# ZYNQ_Power.net
KiCad netlist of a schematic drawn in Altium Designer
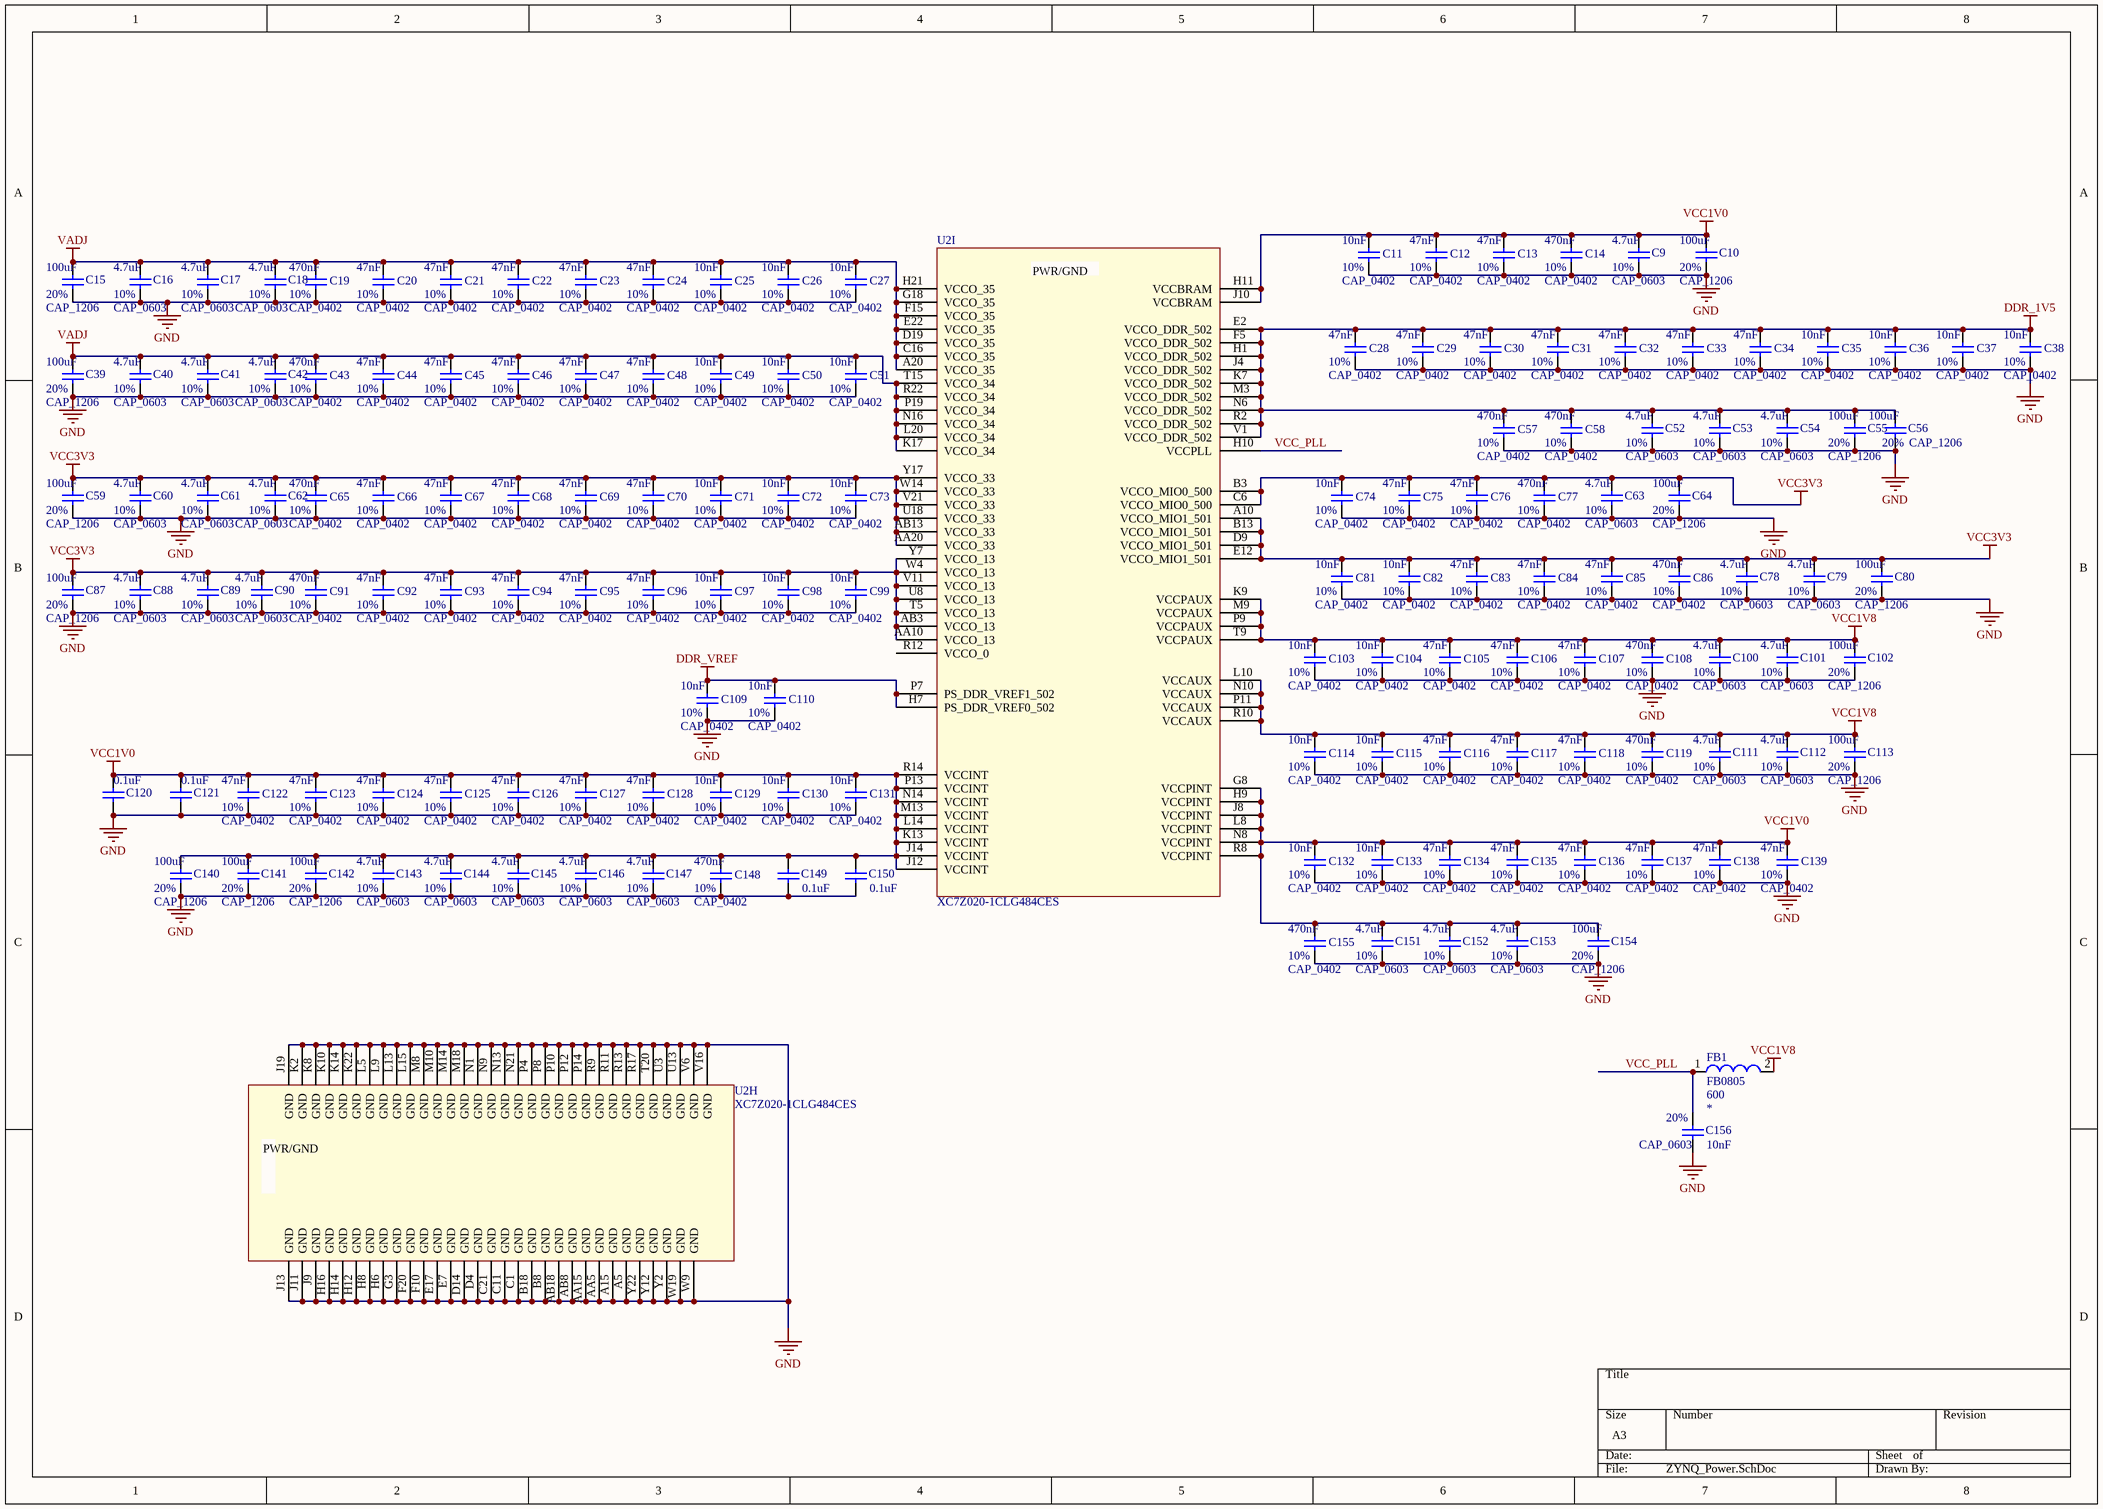
[diagram p0: ZYNQ_Power.SchDoc]

(export (version "E")
  (design (tool "Eeschema 10.0.6"))
  (components
    (comp (ref "C9")
      (value "CAP_0603")
      (footprint "CAPC0603(1608)100_N:CAPC0603(1608)100_N")
      (description "4.7uF, ceramic, 10% 6.3V X5R Low ESR, 0603")
      (fields
        (field (name "ALTIUM_VALUE") "4.7uF")
        (field (name "TOLERANCE") "10%")
        (field (name "PART NUMBER") "GRM188R60J475KE19D")
        (field (name "MANUFACTURER") "Murata Electronics North America")
      )
      (libsource (lib "COMRAD_Database") (part "CAP_0603"))
    )
    (comp (ref "C10")
      (value "CAP_1206")
      (footprint "CAPC1206(3216)100_N:CAPC1206(3216)100_N")
      (description "CAP CER 100UF 6.3V 20% X5R 1206")
      (fields
        (field (name "ALTIUM_VALUE") "100uF")
        (field (name "TOLERANCE") "20%")
        (field (name "PART NUMBER") "JMK316BJ107ML-T")
        (field (name "MANUFACTURER") "Taiyo Yuden")
      )
      (libsource (lib "COMRAD_Database") (part "CAP_1206"))
    )
    (comp (ref "C11")
      (value "CAP_0402")
      (footprint "CAPC0402(1005)60_N:CAPC0402(1005)60_N")
      (description "10000pF, ceramic, 10% 6.3V X5R, 0402")
      (fields
        (field (name "ALTIUM_VALUE") "10nF")
        (field (name "TOLERANCE") "10%")
        (field (name "PART NUMBER") "GRM155R60J103KA01D")
        (field (name "MANUFACTURER") "Murata Electronics North America")
      )
      (libsource (lib "COMRAD_Database") (part "CAP_0402"))
    )
    (comp (ref "C12")
      (value "CAP_0402")
      (footprint "CAPC0402(1005)60_N:CAPC0402(1005)60_N")
      (description "0.047uF, ceramic, 10% 6.3V X5R, 0402")
      (fields
        (field (name "ALTIUM_VALUE") "47nF")
        (field (name "TOLERANCE") "10%")
        (field (name "PART NUMBER") "GRM155R60J473KA01D")
        (field (name "MANUFACTURER") "Murata Electronics North America")
      )
      (libsource (lib "COMRAD_Database") (part "CAP_0402"))
    )
    (comp (ref "C13")
      (value "CAP_0402")
      (footprint "CAPC0402(1005)60_N:CAPC0402(1005)60_N")
      (description "0.047uF, ceramic, 10% 6.3V X5R, 0402")
      (fields
        (field (name "ALTIUM_VALUE") "47nF")
        (field (name "TOLERANCE") "10%")
        (field (name "PART NUMBER") "GRM155R60J473KA01D")
        (field (name "MANUFACTURER") "Murata Electronics North America")
      )
      (libsource (lib "COMRAD_Database") (part "CAP_0402"))
    )
    (comp (ref "C14")
      (value "CAP_0402")
      (footprint "CAPC0402(1005)60_N:CAPC0402(1005)60_N")
      (description "0.47uF, ceramic, 10% 6.3V X5R, 0402")
      (fields
        (field (name "ALTIUM_VALUE") "470nF")
        (field (name "TOLERANCE") "10%")
        (field (name "PART NUMBER") "GRM155R60J474KE19D")
        (field (name "MANUFACTURER") "Murata Electronics North America")
      )
      (libsource (lib "COMRAD_Database") (part "CAP_0402"))
    )
    (comp (ref "C15")
      (value "CAP_1206")
      (footprint "CAPC1206(3216)100_N:CAPC1206(3216)100_N")
      (description "CAP CER 100UF 6.3V 20% X5R 1206")
      (fields
        (field (name "ALTIUM_VALUE") "100uF")
        (field (name "TOLERANCE") "20%")
        (field (name "PART NUMBER") "JMK316BJ107ML-T")
        (field (name "MANUFACTURER") "Taiyo Yuden")
      )
      (libsource (lib "COMRAD_Database") (part "CAP_1206"))
    )
    (comp (ref "C16")
      (value "CAP_0603")
      (footprint "CAPC0603(1608)100_N:CAPC0603(1608)100_N")
      (description "4.7uF, ceramic, 10% 6.3V X5R Low ESR, 0603")
      (fields
        (field (name "ALTIUM_VALUE") "4.7uF")
        (field (name "TOLERANCE") "10%")
        (field (name "PART NUMBER") "GRM188R60J475KE19D")
        (field (name "MANUFACTURER") "Murata Electronics North America")
      )
      (libsource (lib "COMRAD_Database") (part "CAP_0603"))
    )
    (comp (ref "C17")
      (value "CAP_0603")
      (footprint "CAPC0603(1608)100_N:CAPC0603(1608)100_N")
      (description "4.7uF, ceramic, 10% 6.3V X5R Low ESR, 0603")
      (fields
        (field (name "ALTIUM_VALUE") "4.7uF")
        (field (name "TOLERANCE") "10%")
        (field (name "PART NUMBER") "GRM188R60J475KE19D")
        (field (name "MANUFACTURER") "Murata Electronics North America")
      )
      (libsource (lib "COMRAD_Database") (part "CAP_0603"))
    )
    (comp (ref "C18")
      (value "CAP_0603")
      (footprint "CAPC0603(1608)100_N:CAPC0603(1608)100_N")
      (description "4.7uF, ceramic, 10% 6.3V X5R Low ESR, 0603")
      (fields
        (field (name "ALTIUM_VALUE") "4.7uF")
        (field (name "TOLERANCE") "10%")
        (field (name "PART NUMBER") "GRM188R60J475KE19D")
        (field (name "MANUFACTURER") "Murata Electronics North America")
      )
      (libsource (lib "COMRAD_Database") (part "CAP_0603"))
    )
    (comp (ref "C19")
      (value "CAP_0402")
      (footprint "CAPC0402(1005)60_N:CAPC0402(1005)60_N")
      (description "0.47uF, ceramic, 10% 6.3V X5R, 0402")
      (fields
        (field (name "ALTIUM_VALUE") "470nF")
        (field (name "TOLERANCE") "10%")
        (field (name "PART NUMBER") "GRM155R60J474KE19D")
        (field (name "MANUFACTURER") "Murata Electronics North America")
      )
      (libsource (lib "COMRAD_Database") (part "CAP_0402"))
    )
    (comp (ref "C20")
      (value "CAP_0402")
      (footprint "CAPC0402(1005)60_N:CAPC0402(1005)60_N")
      (description "0.047uF, ceramic, 10% 6.3V X5R, 0402")
      (fields
        (field (name "ALTIUM_VALUE") "47nF")
        (field (name "TOLERANCE") "10%")
        (field (name "PART NUMBER") "GRM155R60J473KA01D")
        (field (name "MANUFACTURER") "Murata Electronics North America")
      )
      (libsource (lib "COMRAD_Database") (part "CAP_0402"))
    )
    (comp (ref "C21")
      (value "CAP_0402")
      (footprint "CAPC0402(1005)60_N:CAPC0402(1005)60_N")
      (description "0.047uF, ceramic, 10% 6.3V X5R, 0402")
      (fields
        (field (name "ALTIUM_VALUE") "47nF")
        (field (name "TOLERANCE") "10%")
        (field (name "PART NUMBER") "GRM155R60J473KA01D")
        (field (name "MANUFACTURER") "Murata Electronics North America")
      )
      (libsource (lib "COMRAD_Database") (part "CAP_0402"))
    )
    (comp (ref "C22")
      (value "CAP_0402")
      (footprint "CAPC0402(1005)60_N:CAPC0402(1005)60_N")
      (description "0.047uF, ceramic, 10% 6.3V X5R, 0402")
      (fields
        (field (name "ALTIUM_VALUE") "47nF")
        (field (name "TOLERANCE") "10%")
        (field (name "PART NUMBER") "GRM155R60J473KA01D")
        (field (name "MANUFACTURER") "Murata Electronics North America")
      )
      (libsource (lib "COMRAD_Database") (part "CAP_0402"))
    )
    (comp (ref "C23")
      (value "CAP_0402")
      (footprint "CAPC0402(1005)60_N:CAPC0402(1005)60_N")
      (description "0.047uF, ceramic, 10% 6.3V X5R, 0402")
      (fields
        (field (name "ALTIUM_VALUE") "47nF")
        (field (name "TOLERANCE") "10%")
        (field (name "PART NUMBER") "GRM155R60J473KA01D")
        (field (name "MANUFACTURER") "Murata Electronics North America")
      )
      (libsource (lib "COMRAD_Database") (part "CAP_0402"))
    )
    (comp (ref "C24")
      (value "CAP_0402")
      (footprint "CAPC0402(1005)60_N:CAPC0402(1005)60_N")
      (description "0.047uF, ceramic, 10% 6.3V X5R, 0402")
      (fields
        (field (name "ALTIUM_VALUE") "47nF")
        (field (name "TOLERANCE") "10%")
        (field (name "PART NUMBER") "GRM155R60J473KA01D")
        (field (name "MANUFACTURER") "Murata Electronics North America")
      )
      (libsource (lib "COMRAD_Database") (part "CAP_0402"))
    )
    (comp (ref "C25")
      (value "CAP_0402")
      (footprint "CAPC0402(1005)60_N:CAPC0402(1005)60_N")
      (description "10000pF, ceramic, 10% 6.3V X5R, 0402")
      (fields
        (field (name "ALTIUM_VALUE") "10nF")
        (field (name "TOLERANCE") "10%")
        (field (name "PART NUMBER") "GRM155R60J103KA01D")
        (field (name "MANUFACTURER") "Murata Electronics North America")
      )
      (libsource (lib "COMRAD_Database") (part "CAP_0402"))
    )
    (comp (ref "C26")
      (value "CAP_0402")
      (footprint "CAPC0402(1005)60_N:CAPC0402(1005)60_N")
      (description "10000pF, ceramic, 10% 6.3V X5R, 0402")
      (fields
        (field (name "ALTIUM_VALUE") "10nF")
        (field (name "TOLERANCE") "10%")
        (field (name "PART NUMBER") "GRM155R60J103KA01D")
        (field (name "MANUFACTURER") "Murata Electronics North America")
      )
      (libsource (lib "COMRAD_Database") (part "CAP_0402"))
    )
    (comp (ref "C27")
      (value "CAP_0402")
      (footprint "CAPC0402(1005)60_N:CAPC0402(1005)60_N")
      (description "10000pF, ceramic, 10% 6.3V X5R, 0402")
      (fields
        (field (name "ALTIUM_VALUE") "10nF")
        (field (name "TOLERANCE") "10%")
        (field (name "PART NUMBER") "GRM155R60J103KA01D")
        (field (name "MANUFACTURER") "Murata Electronics North America")
      )
      (libsource (lib "COMRAD_Database") (part "CAP_0402"))
    )
    (comp (ref "C28")
      (value "CAP_0402")
      (footprint "CAPC0402(1005)60_N:CAPC0402(1005)60_N")
      (description "0.047uF, ceramic, 10% 6.3V X5R, 0402")
      (fields
        (field (name "ALTIUM_VALUE") "47nF")
        (field (name "TOLERANCE") "10%")
        (field (name "PART NUMBER") "GRM155R60J473KA01D")
        (field (name "MANUFACTURER") "Murata Electronics North America")
      )
      (libsource (lib "COMRAD_Database") (part "CAP_0402"))
    )
    (comp (ref "C29")
      (value "CAP_0402")
      (footprint "CAPC0402(1005)60_N:CAPC0402(1005)60_N")
      (description "0.047uF, ceramic, 10% 6.3V X5R, 0402")
      (fields
        (field (name "ALTIUM_VALUE") "47nF")
        (field (name "TOLERANCE") "10%")
        (field (name "PART NUMBER") "GRM155R60J473KA01D")
        (field (name "MANUFACTURER") "Murata Electronics North America")
      )
      (libsource (lib "COMRAD_Database") (part "CAP_0402"))
    )
    (comp (ref "C30")
      (value "CAP_0402")
      (footprint "CAPC0402(1005)60_N:CAPC0402(1005)60_N")
      (description "0.047uF, ceramic, 10% 6.3V X5R, 0402")
      (fields
        (field (name "ALTIUM_VALUE") "47nF")
        (field (name "TOLERANCE") "10%")
        (field (name "PART NUMBER") "GRM155R60J473KA01D")
        (field (name "MANUFACTURER") "Murata Electronics North America")
      )
      (libsource (lib "COMRAD_Database") (part "CAP_0402"))
    )
    (comp (ref "C31")
      (value "CAP_0402")
      (footprint "CAPC0402(1005)60_N:CAPC0402(1005)60_N")
      (description "0.047uF, ceramic, 10% 6.3V X5R, 0402")
      (fields
        (field (name "ALTIUM_VALUE") "47nF")
        (field (name "TOLERANCE") "10%")
        (field (name "PART NUMBER") "GRM155R60J473KA01D")
        (field (name "MANUFACTURER") "Murata Electronics North America")
      )
      (libsource (lib "COMRAD_Database") (part "CAP_0402"))
    )
    (comp (ref "C32")
      (value "CAP_0402")
      (footprint "CAPC0402(1005)60_N:CAPC0402(1005)60_N")
      (description "0.047uF, ceramic, 10% 6.3V X5R, 0402")
      (fields
        (field (name "ALTIUM_VALUE") "47nF")
        (field (name "TOLERANCE") "10%")
        (field (name "PART NUMBER") "GRM155R60J473KA01D")
        (field (name "MANUFACTURER") "Murata Electronics North America")
      )
      (libsource (lib "COMRAD_Database") (part "CAP_0402"))
    )
    (comp (ref "C33")
      (value "CAP_0402")
      (footprint "CAPC0402(1005)60_N:CAPC0402(1005)60_N")
      (description "0.047uF, ceramic, 10% 6.3V X5R, 0402")
      (fields
        (field (name "ALTIUM_VALUE") "47nF")
        (field (name "TOLERANCE") "10%")
        (field (name "PART NUMBER") "GRM155R60J473KA01D")
        (field (name "MANUFACTURER") "Murata Electronics North America")
      )
      (libsource (lib "COMRAD_Database") (part "CAP_0402"))
    )
    (comp (ref "C34")
      (value "CAP_0402")
      (footprint "CAPC0402(1005)60_N:CAPC0402(1005)60_N")
      (description "0.047uF, ceramic, 10% 6.3V X5R, 0402")
      (fields
        (field (name "ALTIUM_VALUE") "47nF")
        (field (name "TOLERANCE") "10%")
        (field (name "PART NUMBER") "GRM155R60J473KA01D")
        (field (name "MANUFACTURER") "Murata Electronics North America")
      )
      (libsource (lib "COMRAD_Database") (part "CAP_0402"))
    )
    (comp (ref "C35")
      (value "CAP_0402")
      (footprint "CAPC0402(1005)60_N:CAPC0402(1005)60_N")
      (description "10000pF, ceramic, 10% 6.3V X5R, 0402")
      (fields
        (field (name "ALTIUM_VALUE") "10nF")
        (field (name "TOLERANCE") "10%")
        (field (name "PART NUMBER") "GRM155R60J103KA01D")
        (field (name "MANUFACTURER") "Murata Electronics North America")
      )
      (libsource (lib "COMRAD_Database") (part "CAP_0402"))
    )
    (comp (ref "C36")
      (value "CAP_0402")
      (footprint "CAPC0402(1005)60_N:CAPC0402(1005)60_N")
      (description "10000pF, ceramic, 10% 6.3V X5R, 0402")
      (fields
        (field (name "ALTIUM_VALUE") "10nF")
        (field (name "TOLERANCE") "10%")
        (field (name "PART NUMBER") "GRM155R60J103KA01D")
        (field (name "MANUFACTURER") "Murata Electronics North America")
      )
      (libsource (lib "COMRAD_Database") (part "CAP_0402"))
    )
    (comp (ref "C37")
      (value "CAP_0402")
      (footprint "CAPC0402(1005)60_N:CAPC0402(1005)60_N")
      (description "10000pF, ceramic, 10% 6.3V X5R, 0402")
      (fields
        (field (name "ALTIUM_VALUE") "10nF")
        (field (name "TOLERANCE") "10%")
        (field (name "PART NUMBER") "GRM155R60J103KA01D")
        (field (name "MANUFACTURER") "Murata Electronics North America")
      )
      (libsource (lib "COMRAD_Database") (part "CAP_0402"))
    )
    (comp (ref "C38")
      (value "CAP_0402")
      (footprint "CAPC0402(1005)60_N:CAPC0402(1005)60_N")
      (description "10000pF, ceramic, 10% 6.3V X5R, 0402")
      (fields
        (field (name "ALTIUM_VALUE") "10nF")
        (field (name "TOLERANCE") "10%")
        (field (name "PART NUMBER") "GRM155R60J103KA01D")
        (field (name "MANUFACTURER") "Murata Electronics North America")
      )
      (libsource (lib "COMRAD_Database") (part "CAP_0402"))
    )
    (comp (ref "C39")
      (value "CAP_1206")
      (footprint "CAPC1206(3216)100_N:CAPC1206(3216)100_N")
      (description "CAP CER 100UF 6.3V 20% X5R 1206")
      (fields
        (field (name "ALTIUM_VALUE") "100uF")
        (field (name "TOLERANCE") "20%")
        (field (name "PART NUMBER") "JMK316BJ107ML-T")
        (field (name "MANUFACTURER") "Taiyo Yuden")
      )
      (libsource (lib "COMRAD_Database") (part "CAP_1206"))
    )
    (comp (ref "C40")
      (value "CAP_0603")
      (footprint "CAPC0603(1608)100_N:CAPC0603(1608)100_N")
      (description "4.7uF, ceramic, 10% 6.3V X5R Low ESR, 0603")
      (fields
        (field (name "ALTIUM_VALUE") "4.7uF")
        (field (name "TOLERANCE") "10%")
        (field (name "PART NUMBER") "GRM188R60J475KE19D")
        (field (name "MANUFACTURER") "Murata Electronics North America")
      )
      (libsource (lib "COMRAD_Database") (part "CAP_0603"))
    )
    (comp (ref "C41")
      (value "CAP_0603")
      (footprint "CAPC0603(1608)100_N:CAPC0603(1608)100_N")
      (description "4.7uF, ceramic, 10% 6.3V X5R Low ESR, 0603")
      (fields
        (field (name "ALTIUM_VALUE") "4.7uF")
        (field (name "TOLERANCE") "10%")
        (field (name "PART NUMBER") "GRM188R60J475KE19D")
        (field (name "MANUFACTURER") "Murata Electronics North America")
      )
      (libsource (lib "COMRAD_Database") (part "CAP_0603"))
    )
    (comp (ref "C42")
      (value "CAP_0603")
      (footprint "CAPC0603(1608)100_N:CAPC0603(1608)100_N")
      (description "4.7uF, ceramic, 10% 6.3V X5R Low ESR, 0603")
      (fields
        (field (name "ALTIUM_VALUE") "4.7uF")
        (field (name "TOLERANCE") "10%")
        (field (name "PART NUMBER") "GRM188R60J475KE19D")
        (field (name "MANUFACTURER") "Murata Electronics North America")
      )
      (libsource (lib "COMRAD_Database") (part "CAP_0603"))
    )
    (comp (ref "C43")
      (value "CAP_0402")
      (footprint "CAPC0402(1005)60_N:CAPC0402(1005)60_N")
      (description "0.47uF, ceramic, 10% 6.3V X5R, 0402")
      (fields
        (field (name "ALTIUM_VALUE") "470nF")
        (field (name "TOLERANCE") "10%")
        (field (name "PART NUMBER") "GRM155R60J474KE19D")
        (field (name "MANUFACTURER") "Murata Electronics North America")
      )
      (libsource (lib "COMRAD_Database") (part "CAP_0402"))
    )
    (comp (ref "C44")
      (value "CAP_0402")
      (footprint "CAPC0402(1005)60_N:CAPC0402(1005)60_N")
      (description "0.047uF, ceramic, 10% 6.3V X5R, 0402")
      (fields
        (field (name "ALTIUM_VALUE") "47nF")
        (field (name "TOLERANCE") "10%")
        (field (name "PART NUMBER") "GRM155R60J473KA01D")
        (field (name "MANUFACTURER") "Murata Electronics North America")
      )
      (libsource (lib "COMRAD_Database") (part "CAP_0402"))
    )
    (comp (ref "C45")
      (value "CAP_0402")
      (footprint "CAPC0402(1005)60_N:CAPC0402(1005)60_N")
      (description "0.047uF, ceramic, 10% 6.3V X5R, 0402")
      (fields
        (field (name "ALTIUM_VALUE") "47nF")
        (field (name "TOLERANCE") "10%")
        (field (name "PART NUMBER") "GRM155R60J473KA01D")
        (field (name "MANUFACTURER") "Murata Electronics North America")
      )
      (libsource (lib "COMRAD_Database") (part "CAP_0402"))
    )
    (comp (ref "C46")
      (value "CAP_0402")
      (footprint "CAPC0402(1005)60_N:CAPC0402(1005)60_N")
      (description "0.047uF, ceramic, 10% 6.3V X5R, 0402")
      (fields
        (field (name "ALTIUM_VALUE") "47nF")
        (field (name "TOLERANCE") "10%")
        (field (name "PART NUMBER") "GRM155R60J473KA01D")
        (field (name "MANUFACTURER") "Murata Electronics North America")
      )
      (libsource (lib "COMRAD_Database") (part "CAP_0402"))
    )
    (comp (ref "C47")
      (value "CAP_0402")
      (footprint "CAPC0402(1005)60_N:CAPC0402(1005)60_N")
      (description "0.047uF, ceramic, 10% 6.3V X5R, 0402")
      (fields
        (field (name "ALTIUM_VALUE") "47nF")
        (field (name "TOLERANCE") "10%")
        (field (name "PART NUMBER") "GRM155R60J473KA01D")
        (field (name "MANUFACTURER") "Murata Electronics North America")
      )
      (libsource (lib "COMRAD_Database") (part "CAP_0402"))
    )
    (comp (ref "C48")
      (value "CAP_0402")
      (footprint "CAPC0402(1005)60_N:CAPC0402(1005)60_N")
      (description "0.047uF, ceramic, 10% 6.3V X5R, 0402")
      (fields
        (field (name "ALTIUM_VALUE") "47nF")
        (field (name "TOLERANCE") "10%")
        (field (name "PART NUMBER") "GRM155R60J473KA01D")
        (field (name "MANUFACTURER") "Murata Electronics North America")
      )
      (libsource (lib "COMRAD_Database") (part "CAP_0402"))
    )
    (comp (ref "C49")
      (value "CAP_0402")
      (footprint "CAPC0402(1005)60_N:CAPC0402(1005)60_N")
      (description "10000pF, ceramic, 10% 6.3V X5R, 0402")
      (fields
        (field (name "ALTIUM_VALUE") "10nF")
        (field (name "TOLERANCE") "10%")
        (field (name "PART NUMBER") "GRM155R60J103KA01D")
        (field (name "MANUFACTURER") "Murata Electronics North America")
      )
      (libsource (lib "COMRAD_Database") (part "CAP_0402"))
    )
    (comp (ref "C50")
      (value "CAP_0402")
      (footprint "CAPC0402(1005)60_N:CAPC0402(1005)60_N")
      (description "10000pF, ceramic, 10% 6.3V X5R, 0402")
      (fields
        (field (name "ALTIUM_VALUE") "10nF")
        (field (name "TOLERANCE") "10%")
        (field (name "PART NUMBER") "GRM155R60J103KA01D")
        (field (name "MANUFACTURER") "Murata Electronics North America")
      )
      (libsource (lib "COMRAD_Database") (part "CAP_0402"))
    )
    (comp (ref "C51")
      (value "CAP_0402")
      (footprint "CAPC0402(1005)60_N:CAPC0402(1005)60_N")
      (description "10000pF, ceramic, 10% 6.3V X5R, 0402")
      (fields
        (field (name "ALTIUM_VALUE") "10nF")
        (field (name "TOLERANCE") "10%")
        (field (name "PART NUMBER") "GRM155R60J103KA01D")
        (field (name "MANUFACTURER") "Murata Electronics North America")
      )
      (libsource (lib "COMRAD_Database") (part "CAP_0402"))
    )
    (comp (ref "C52")
      (value "CAP_0603")
      (footprint "CAPC0603(1608)100_N:CAPC0603(1608)100_N")
      (description "4.7uF, ceramic, 10% 6.3V X5R Low ESR, 0603")
      (fields
        (field (name "ALTIUM_VALUE") "4.7uF")
        (field (name "TOLERANCE") "10%")
        (field (name "PART NUMBER") "GRM188R60J475KE19D")
        (field (name "MANUFACTURER") "Murata Electronics North America")
      )
      (libsource (lib "COMRAD_Database") (part "CAP_0603"))
    )
    (comp (ref "C53")
      (value "CAP_0603")
      (footprint "CAPC0603(1608)100_N:CAPC0603(1608)100_N")
      (description "4.7uF, ceramic, 10% 6.3V X5R Low ESR, 0603")
      (fields
        (field (name "ALTIUM_VALUE") "4.7uF")
        (field (name "TOLERANCE") "10%")
        (field (name "PART NUMBER") "GRM188R60J475KE19D")
        (field (name "MANUFACTURER") "Murata Electronics North America")
      )
      (libsource (lib "COMRAD_Database") (part "CAP_0603"))
    )
    (comp (ref "C54")
      (value "CAP_0603")
      (footprint "CAPC0603(1608)100_N:CAPC0603(1608)100_N")
      (description "4.7uF, ceramic, 10% 6.3V X5R Low ESR, 0603")
      (fields
        (field (name "ALTIUM_VALUE") "4.7uF")
        (field (name "TOLERANCE") "10%")
        (field (name "PART NUMBER") "GRM188R60J475KE19D")
        (field (name "MANUFACTURER") "Murata Electronics North America")
      )
      (libsource (lib "COMRAD_Database") (part "CAP_0603"))
    )
    (comp (ref "C55")
      (value "CAP_1206")
      (footprint "CAPC1206(3216)100_N:CAPC1206(3216)100_N")
      (description "CAP CER 100UF 6.3V 20% X5R 1206")
      (fields
        (field (name "ALTIUM_VALUE") "100uF")
        (field (name "TOLERANCE") "20%")
        (field (name "PART NUMBER") "JMK316BJ107ML-T")
        (field (name "MANUFACTURER") "Taiyo Yuden")
      )
      (libsource (lib "COMRAD_Database") (part "CAP_1206"))
    )
    (comp (ref "C56")
      (value "CAP_1206")
      (footprint "CAPC1206(3216)100_N:CAPC1206(3216)100_N")
      (description "CAP CER 100UF 6.3V 20% X5R 1206")
      (fields
        (field (name "ALTIUM_VALUE") "100uF")
        (field (name "TOLERANCE") "20%")
        (field (name "PART NUMBER") "JMK316BJ107ML-T")
        (field (name "MANUFACTURER") "Taiyo Yuden")
      )
      (libsource (lib "COMRAD_Database") (part "CAP_1206"))
    )
    (comp (ref "C57")
      (value "CAP_0402")
      (footprint "CAPC0402(1005)60_N:CAPC0402(1005)60_N")
      (description "0.47uF, ceramic, 10% 6.3V X5R, 0402")
      (fields
        (field (name "ALTIUM_VALUE") "470nF")
        (field (name "TOLERANCE") "10%")
        (field (name "PART NUMBER") "GRM155R60J474KE19D")
        (field (name "MANUFACTURER") "Murata Electronics North America")
      )
      (libsource (lib "COMRAD_Database") (part "CAP_0402"))
    )
    (comp (ref "C58")
      (value "CAP_0402")
      (footprint "CAPC0402(1005)60_N:CAPC0402(1005)60_N")
      (description "0.47uF, ceramic, 10% 6.3V X5R, 0402")
      (fields
        (field (name "ALTIUM_VALUE") "470nF")
        (field (name "TOLERANCE") "10%")
        (field (name "PART NUMBER") "GRM155R60J474KE19D")
        (field (name "MANUFACTURER") "Murata Electronics North America")
      )
      (libsource (lib "COMRAD_Database") (part "CAP_0402"))
    )
    (comp (ref "C59")
      (value "CAP_1206")
      (footprint "CAPC1206(3216)100_N:CAPC1206(3216)100_N")
      (description "CAP CER 100UF 6.3V 20% X5R 1206")
      (fields
        (field (name "ALTIUM_VALUE") "100uF")
        (field (name "TOLERANCE") "20%")
        (field (name "PART NUMBER") "JMK316BJ107ML-T")
        (field (name "MANUFACTURER") "Taiyo Yuden")
      )
      (libsource (lib "COMRAD_Database") (part "CAP_1206"))
    )
    (comp (ref "C60")
      (value "CAP_0603")
      (footprint "CAPC0603(1608)100_N:CAPC0603(1608)100_N")
      (description "4.7uF, ceramic, 10% 6.3V X5R Low ESR, 0603")
      (fields
        (field (name "ALTIUM_VALUE") "4.7uF")
        (field (name "TOLERANCE") "10%")
        (field (name "PART NUMBER") "GRM188R60J475KE19D")
        (field (name "MANUFACTURER") "Murata Electronics North America")
      )
      (libsource (lib "COMRAD_Database") (part "CAP_0603"))
    )
    (comp (ref "C61")
      (value "CAP_0603")
      (footprint "CAPC0603(1608)100_N:CAPC0603(1608)100_N")
      (description "4.7uF, ceramic, 10% 6.3V X5R Low ESR, 0603")
      (fields
        (field (name "ALTIUM_VALUE") "4.7uF")
        (field (name "TOLERANCE") "10%")
        (field (name "PART NUMBER") "GRM188R60J475KE19D")
        (field (name "MANUFACTURER") "Murata Electronics North America")
      )
      (libsource (lib "COMRAD_Database") (part "CAP_0603"))
    )
    (comp (ref "C62")
      (value "CAP_0603")
      (footprint "CAPC0603(1608)100_N:CAPC0603(1608)100_N")
      (description "4.7uF, ceramic, 10% 6.3V X5R Low ESR, 0603")
      (fields
        (field (name "ALTIUM_VALUE") "4.7uF")
        (field (name "TOLERANCE") "10%")
        (field (name "PART NUMBER") "GRM188R60J475KE19D")
        (field (name "MANUFACTURER") "Murata Electronics North America")
      )
      (libsource (lib "COMRAD_Database") (part "CAP_0603"))
    )
    (comp (ref "C63")
      (value "CAP_0603")
      (footprint "CAPC0603(1608)100_N:CAPC0603(1608)100_N")
      (description "4.7uF, ceramic, 10% 6.3V X5R Low ESR, 0603")
      (fields
        (field (name "ALTIUM_VALUE") "4.7uF")
        (field (name "TOLERANCE") "10%")
        (field (name "PART NUMBER") "GRM188R60J475KE19D")
        (field (name "MANUFACTURER") "Murata Electronics North America")
      )
      (libsource (lib "COMRAD_Database") (part "CAP_0603"))
    )
    (comp (ref "C64")
      (value "CAP_1206")
      (footprint "CAPC1206(3216)100_N:CAPC1206(3216)100_N")
      (description "CAP CER 100UF 6.3V 20% X5R 1206")
      (fields
        (field (name "ALTIUM_VALUE") "100uF")
        (field (name "TOLERANCE") "20%")
        (field (name "PART NUMBER") "JMK316BJ107ML-T")
        (field (name "MANUFACTURER") "Taiyo Yuden")
      )
      (libsource (lib "COMRAD_Database") (part "CAP_1206"))
    )
    (comp (ref "C65")
      (value "CAP_0402")
      (footprint "CAPC0402(1005)60_N:CAPC0402(1005)60_N")
      (description "0.47uF, ceramic, 10% 6.3V X5R, 0402")
      (fields
        (field (name "ALTIUM_VALUE") "470nF")
        (field (name "TOLERANCE") "10%")
        (field (name "PART NUMBER") "GRM155R60J474KE19D")
        (field (name "MANUFACTURER") "Murata Electronics North America")
      )
      (libsource (lib "COMRAD_Database") (part "CAP_0402"))
    )
    (comp (ref "C66")
      (value "CAP_0402")
      (footprint "CAPC0402(1005)60_N:CAPC0402(1005)60_N")
      (description "0.047uF, ceramic, 10% 6.3V X5R, 0402")
      (fields
        (field (name "ALTIUM_VALUE") "47nF")
        (field (name "TOLERANCE") "10%")
        (field (name "PART NUMBER") "GRM155R60J473KA01D")
        (field (name "MANUFACTURER") "Murata Electronics North America")
      )
      (libsource (lib "COMRAD_Database") (part "CAP_0402"))
    )
    (comp (ref "C67")
      (value "CAP_0402")
      (footprint "CAPC0402(1005)60_N:CAPC0402(1005)60_N")
      (description "0.047uF, ceramic, 10% 6.3V X5R, 0402")
      (fields
        (field (name "ALTIUM_VALUE") "47nF")
        (field (name "TOLERANCE") "10%")
        (field (name "PART NUMBER") "GRM155R60J473KA01D")
        (field (name "MANUFACTURER") "Murata Electronics North America")
      )
      (libsource (lib "COMRAD_Database") (part "CAP_0402"))
    )
    (comp (ref "C68")
      (value "CAP_0402")
      (footprint "CAPC0402(1005)60_N:CAPC0402(1005)60_N")
      (description "0.047uF, ceramic, 10% 6.3V X5R, 0402")
      (fields
        (field (name "ALTIUM_VALUE") "47nF")
        (field (name "TOLERANCE") "10%")
        (field (name "PART NUMBER") "GRM155R60J473KA01D")
        (field (name "MANUFACTURER") "Murata Electronics North America")
      )
      (libsource (lib "COMRAD_Database") (part "CAP_0402"))
    )
    (comp (ref "C69")
      (value "CAP_0402")
      (footprint "CAPC0402(1005)60_N:CAPC0402(1005)60_N")
      (description "0.047uF, ceramic, 10% 6.3V X5R, 0402")
      (fields
        (field (name "ALTIUM_VALUE") "47nF")
        (field (name "TOLERANCE") "10%")
        (field (name "PART NUMBER") "GRM155R60J473KA01D")
        (field (name "MANUFACTURER") "Murata Electronics North America")
      )
      (libsource (lib "COMRAD_Database") (part "CAP_0402"))
    )
    (comp (ref "C70")
      (value "CAP_0402")
      (footprint "CAPC0402(1005)60_N:CAPC0402(1005)60_N")
      (description "0.047uF, ceramic, 10% 6.3V X5R, 0402")
      (fields
        (field (name "ALTIUM_VALUE") "47nF")
        (field (name "TOLERANCE") "10%")
        (field (name "PART NUMBER") "GRM155R60J473KA01D")
        (field (name "MANUFACTURER") "Murata Electronics North America")
      )
      (libsource (lib "COMRAD_Database") (part "CAP_0402"))
    )
    (comp (ref "C71")
      (value "CAP_0402")
      (footprint "CAPC0402(1005)60_N:CAPC0402(1005)60_N")
      (description "10000pF, ceramic, 10% 6.3V X5R, 0402")
      (fields
        (field (name "ALTIUM_VALUE") "10nF")
        (field (name "TOLERANCE") "10%")
        (field (name "PART NUMBER") "GRM155R60J103KA01D")
        (field (name "MANUFACTURER") "Murata Electronics North America")
      )
      (libsource (lib "COMRAD_Database") (part "CAP_0402"))
    )
    (comp (ref "C72")
      (value "CAP_0402")
      (footprint "CAPC0402(1005)60_N:CAPC0402(1005)60_N")
      (description "10000pF, ceramic, 10% 6.3V X5R, 0402")
      (fields
        (field (name "ALTIUM_VALUE") "10nF")
        (field (name "TOLERANCE") "10%")
        (field (name "PART NUMBER") "GRM155R60J103KA01D")
        (field (name "MANUFACTURER") "Murata Electronics North America")
      )
      (libsource (lib "COMRAD_Database") (part "CAP_0402"))
    )
    (comp (ref "C73")
      (value "CAP_0402")
      (footprint "CAPC0402(1005)60_N:CAPC0402(1005)60_N")
      (description "10000pF, ceramic, 10% 6.3V X5R, 0402")
      (fields
        (field (name "ALTIUM_VALUE") "10nF")
        (field (name "TOLERANCE") "10%")
        (field (name "PART NUMBER") "GRM155R60J103KA01D")
        (field (name "MANUFACTURER") "Murata Electronics North America")
      )
      (libsource (lib "COMRAD_Database") (part "CAP_0402"))
    )
    (comp (ref "C74")
      (value "CAP_0402")
      (footprint "CAPC0402(1005)60_N:CAPC0402(1005)60_N")
      (description "10000pF, ceramic, 10% 6.3V X5R, 0402")
      (fields
        (field (name "ALTIUM_VALUE") "10nF")
        (field (name "TOLERANCE") "10%")
        (field (name "PART NUMBER") "GRM155R60J103KA01D")
        (field (name "MANUFACTURER") "Murata Electronics North America")
      )
      (libsource (lib "COMRAD_Database") (part "CAP_0402"))
    )
    (comp (ref "C75")
      (value "CAP_0402")
      (footprint "CAPC0402(1005)60_N:CAPC0402(1005)60_N")
      (description "0.047uF, ceramic, 10% 6.3V X5R, 0402")
      (fields
        (field (name "ALTIUM_VALUE") "47nF")
        (field (name "TOLERANCE") "10%")
        (field (name "PART NUMBER") "GRM155R60J473KA01D")
        (field (name "MANUFACTURER") "Murata Electronics North America")
      )
      (libsource (lib "COMRAD_Database") (part "CAP_0402"))
    )
    (comp (ref "C76")
      (value "CAP_0402")
      (footprint "CAPC0402(1005)60_N:CAPC0402(1005)60_N")
      (description "0.047uF, ceramic, 10% 6.3V X5R, 0402")
      (fields
        (field (name "ALTIUM_VALUE") "47nF")
        (field (name "TOLERANCE") "10%")
        (field (name "PART NUMBER") "GRM155R60J473KA01D")
        (field (name "MANUFACTURER") "Murata Electronics North America")
      )
      (libsource (lib "COMRAD_Database") (part "CAP_0402"))
    )
    (comp (ref "C77")
      (value "CAP_0402")
      (footprint "CAPC0402(1005)60_N:CAPC0402(1005)60_N")
      (description "0.47uF, ceramic, 10% 6.3V X5R, 0402")
      (fields
        (field (name "ALTIUM_VALUE") "470nF")
        (field (name "TOLERANCE") "10%")
        (field (name "PART NUMBER") "GRM155R60J474KE19D")
        (field (name "MANUFACTURER") "Murata Electronics North America")
      )
      (libsource (lib "COMRAD_Database") (part "CAP_0402"))
    )
    (comp (ref "C78")
      (value "CAP_0603")
      (footprint "CAPC0603(1608)100_N:CAPC0603(1608)100_N")
      (description "4.7uF, ceramic, 10% 6.3V X5R Low ESR, 0603")
      (fields
        (field (name "ALTIUM_VALUE") "4.7uF")
        (field (name "TOLERANCE") "10%")
        (field (name "PART NUMBER") "GRM188R60J475KE19D")
        (field (name "MANUFACTURER") "Murata Electronics North America")
      )
      (libsource (lib "COMRAD_Database") (part "CAP_0603"))
    )
    (comp (ref "C79")
      (value "CAP_0603")
      (footprint "CAPC0603(1608)100_N:CAPC0603(1608)100_N")
      (description "4.7uF, ceramic, 10% 6.3V X5R Low ESR, 0603")
      (fields
        (field (name "ALTIUM_VALUE") "4.7uF")
        (field (name "TOLERANCE") "10%")
        (field (name "PART NUMBER") "GRM188R60J475KE19D")
        (field (name "MANUFACTURER") "Murata Electronics North America")
      )
      (libsource (lib "COMRAD_Database") (part "CAP_0603"))
    )
    (comp (ref "C80")
      (value "CAP_1206")
      (footprint "CAPC1206(3216)100_N:CAPC1206(3216)100_N")
      (description "CAP CER 100UF 6.3V 20% X5R 1206")
      (fields
        (field (name "ALTIUM_VALUE") "100uF")
        (field (name "TOLERANCE") "20%")
        (field (name "PART NUMBER") "JMK316BJ107ML-T")
        (field (name "MANUFACTURER") "Taiyo Yuden")
      )
      (libsource (lib "COMRAD_Database") (part "CAP_1206"))
    )
    (comp (ref "C81")
      (value "CAP_0402")
      (footprint "CAPC0402(1005)60_N:CAPC0402(1005)60_N")
      (description "10000pF, ceramic, 10% 6.3V X5R, 0402")
      (fields
        (field (name "ALTIUM_VALUE") "10nF")
        (field (name "TOLERANCE") "10%")
        (field (name "PART NUMBER") "GRM155R60J103KA01D")
        (field (name "MANUFACTURER") "Murata Electronics North America")
      )
      (libsource (lib "COMRAD_Database") (part "CAP_0402"))
    )
    (comp (ref "C82")
      (value "CAP_0402")
      (footprint "CAPC0402(1005)60_N:CAPC0402(1005)60_N")
      (description "10000pF, ceramic, 10% 6.3V X5R, 0402")
      (fields
        (field (name "ALTIUM_VALUE") "10nF")
        (field (name "TOLERANCE") "10%")
        (field (name "PART NUMBER") "GRM155R60J103KA01D")
        (field (name "MANUFACTURER") "Murata Electronics North America")
      )
      (libsource (lib "COMRAD_Database") (part "CAP_0402"))
    )
    (comp (ref "C83")
      (value "CAP_0402")
      (footprint "CAPC0402(1005)60_N:CAPC0402(1005)60_N")
      (description "0.047uF, ceramic, 10% 6.3V X5R, 0402")
      (fields
        (field (name "ALTIUM_VALUE") "47nF")
        (field (name "TOLERANCE") "10%")
        (field (name "PART NUMBER") "GRM155R60J473KA01D")
        (field (name "MANUFACTURER") "Murata Electronics North America")
      )
      (libsource (lib "COMRAD_Database") (part "CAP_0402"))
    )
    (comp (ref "C84")
      (value "CAP_0402")
      (footprint "CAPC0402(1005)60_N:CAPC0402(1005)60_N")
      (description "0.047uF, ceramic, 10% 6.3V X5R, 0402")
      (fields
        (field (name "ALTIUM_VALUE") "47nF")
        (field (name "TOLERANCE") "10%")
        (field (name "PART NUMBER") "GRM155R60J473KA01D")
        (field (name "MANUFACTURER") "Murata Electronics North America")
      )
      (libsource (lib "COMRAD_Database") (part "CAP_0402"))
    )
    (comp (ref "C85")
      (value "CAP_0402")
      (footprint "CAPC0402(1005)60_N:CAPC0402(1005)60_N")
      (description "0.047uF, ceramic, 10% 6.3V X5R, 0402")
      (fields
        (field (name "ALTIUM_VALUE") "47nF")
        (field (name "TOLERANCE") "10%")
        (field (name "PART NUMBER") "GRM155R60J473KA01D")
        (field (name "MANUFACTURER") "Murata Electronics North America")
      )
      (libsource (lib "COMRAD_Database") (part "CAP_0402"))
    )
    (comp (ref "C86")
      (value "CAP_0402")
      (footprint "CAPC0402(1005)60_N:CAPC0402(1005)60_N")
      (description "0.47uF, ceramic, 10% 6.3V X5R, 0402")
      (fields
        (field (name "ALTIUM_VALUE") "470nF")
        (field (name "TOLERANCE") "10%")
        (field (name "PART NUMBER") "GRM155R60J474KE19D")
        (field (name "MANUFACTURER") "Murata Electronics North America")
      )
      (libsource (lib "COMRAD_Database") (part "CAP_0402"))
    )
    (comp (ref "C87")
      (value "CAP_1206")
      (footprint "CAPC1206(3216)100_N:CAPC1206(3216)100_N")
      (description "CAP CER 100UF 6.3V 20% X5R 1206")
      (fields
        (field (name "ALTIUM_VALUE") "100uF")
        (field (name "TOLERANCE") "20%")
        (field (name "PART NUMBER") "JMK316BJ107ML-T")
        (field (name "MANUFACTURER") "Taiyo Yuden")
      )
      (libsource (lib "COMRAD_Database") (part "CAP_1206"))
    )
    (comp (ref "C88")
      (value "CAP_0603")
      (footprint "CAPC0603(1608)100_N:CAPC0603(1608)100_N")
      (description "4.7uF, ceramic, 10% 6.3V X5R Low ESR, 0603")
      (fields
        (field (name "ALTIUM_VALUE") "4.7uF")
        (field (name "TOLERANCE") "10%")
        (field (name "PART NUMBER") "GRM188R60J475KE19D")
        (field (name "MANUFACTURER") "Murata Electronics North America")
      )
      (libsource (lib "COMRAD_Database") (part "CAP_0603"))
    )
    (comp (ref "C89")
      (value "CAP_0603")
      (footprint "CAPC0603(1608)100_N:CAPC0603(1608)100_N")
      (description "4.7uF, ceramic, 10% 6.3V X5R Low ESR, 0603")
      (fields
        (field (name "ALTIUM_VALUE") "4.7uF")
        (field (name "TOLERANCE") "10%")
        (field (name "PART NUMBER") "GRM188R60J475KE19D")
        (field (name "MANUFACTURER") "Murata Electronics North America")
      )
      (libsource (lib "COMRAD_Database") (part "CAP_0603"))
    )
    (comp (ref "C90")
      (value "CAP_0603")
      (footprint "CAPC0603(1608)100_N:CAPC0603(1608)100_N")
      (description "4.7uF, ceramic, 10% 6.3V X5R Low ESR, 0603")
      (fields
        (field (name "ALTIUM_VALUE") "4.7uF")
        (field (name "TOLERANCE") "10%")
        (field (name "PART NUMBER") "GRM188R60J475KE19D")
        (field (name "MANUFACTURER") "Murata Electronics North America")
      )
      (libsource (lib "COMRAD_Database") (part "CAP_0603"))
    )
    (comp (ref "C91")
      (value "CAP_0402")
      (footprint "CAPC0402(1005)60_N:CAPC0402(1005)60_N")
      (description "0.47uF, ceramic, 10% 6.3V X5R, 0402")
      (fields
        (field (name "ALTIUM_VALUE") "470nF")
        (field (name "TOLERANCE") "10%")
        (field (name "PART NUMBER") "GRM155R60J474KE19D")
        (field (name "MANUFACTURER") "Murata Electronics North America")
      )
      (libsource (lib "COMRAD_Database") (part "CAP_0402"))
    )
    (comp (ref "C92")
      (value "CAP_0402")
      (footprint "CAPC0402(1005)60_N:CAPC0402(1005)60_N")
      (description "0.047uF, ceramic, 10% 6.3V X5R, 0402")
      (fields
        (field (name "ALTIUM_VALUE") "47nF")
        (field (name "TOLERANCE") "10%")
        (field (name "PART NUMBER") "GRM155R60J473KA01D")
        (field (name "MANUFACTURER") "Murata Electronics North America")
      )
      (libsource (lib "COMRAD_Database") (part "CAP_0402"))
    )
    (comp (ref "C93")
      (value "CAP_0402")
      (footprint "CAPC0402(1005)60_N:CAPC0402(1005)60_N")
      (description "0.047uF, ceramic, 10% 6.3V X5R, 0402")
      (fields
        (field (name "ALTIUM_VALUE") "47nF")
        (field (name "TOLERANCE") "10%")
        (field (name "PART NUMBER") "GRM155R60J473KA01D")
        (field (name "MANUFACTURER") "Murata Electronics North America")
      )
      (libsource (lib "COMRAD_Database") (part "CAP_0402"))
    )
    (comp (ref "C94")
      (value "CAP_0402")
      (footprint "CAPC0402(1005)60_N:CAPC0402(1005)60_N")
      (description "0.047uF, ceramic, 10% 6.3V X5R, 0402")
      (fields
        (field (name "ALTIUM_VALUE") "47nF")
        (field (name "TOLERANCE") "10%")
        (field (name "PART NUMBER") "GRM155R60J473KA01D")
        (field (name "MANUFACTURER") "Murata Electronics North America")
      )
      (libsource (lib "COMRAD_Database") (part "CAP_0402"))
    )
    (comp (ref "C95")
      (value "CAP_0402")
      (footprint "CAPC0402(1005)60_N:CAPC0402(1005)60_N")
      (description "0.047uF, ceramic, 10% 6.3V X5R, 0402")
      (fields
        (field (name "ALTIUM_VALUE") "47nF")
        (field (name "TOLERANCE") "10%")
        (field (name "PART NUMBER") "GRM155R60J473KA01D")
        (field (name "MANUFACTURER") "Murata Electronics North America")
      )
      (libsource (lib "COMRAD_Database") (part "CAP_0402"))
    )
    (comp (ref "C96")
      (value "CAP_0402")
      (footprint "CAPC0402(1005)60_N:CAPC0402(1005)60_N")
      (description "0.047uF, ceramic, 10% 6.3V X5R, 0402")
      (fields
        (field (name "ALTIUM_VALUE") "47nF")
        (field (name "TOLERANCE") "10%")
        (field (name "PART NUMBER") "GRM155R60J473KA01D")
        (field (name "MANUFACTURER") "Murata Electronics North America")
      )
      (libsource (lib "COMRAD_Database") (part "CAP_0402"))
    )
    (comp (ref "C97")
      (value "CAP_0402")
      (footprint "CAPC0402(1005)60_N:CAPC0402(1005)60_N")
      (description "10000pF, ceramic, 10% 6.3V X5R, 0402")
      (fields
        (field (name "ALTIUM_VALUE") "10nF")
        (field (name "TOLERANCE") "10%")
        (field (name "PART NUMBER") "GRM155R60J103KA01D")
        (field (name "MANUFACTURER") "Murata Electronics North America")
      )
      (libsource (lib "COMRAD_Database") (part "CAP_0402"))
    )
    (comp (ref "C98")
      (value "CAP_0402")
      (footprint "CAPC0402(1005)60_N:CAPC0402(1005)60_N")
      (description "10000pF, ceramic, 10% 6.3V X5R, 0402")
      (fields
        (field (name "ALTIUM_VALUE") "10nF")
        (field (name "TOLERANCE") "10%")
        (field (name "PART NUMBER") "GRM155R60J103KA01D")
        (field (name "MANUFACTURER") "Murata Electronics North America")
      )
      (libsource (lib "COMRAD_Database") (part "CAP_0402"))
    )
    (comp (ref "C99")
      (value "CAP_0402")
      (footprint "CAPC0402(1005)60_N:CAPC0402(1005)60_N")
      (description "10000pF, ceramic, 10% 6.3V X5R, 0402")
      (fields
        (field (name "ALTIUM_VALUE") "10nF")
        (field (name "TOLERANCE") "10%")
        (field (name "PART NUMBER") "GRM155R60J103KA01D")
        (field (name "MANUFACTURER") "Murata Electronics North America")
      )
      (libsource (lib "COMRAD_Database") (part "CAP_0402"))
    )
    (comp (ref "C100")
      (value "CAP_0603")
      (footprint "CAPC0603(1608)100_N:CAPC0603(1608)100_N")
      (description "4.7uF, ceramic, 10% 6.3V X5R Low ESR, 0603")
      (fields
        (field (name "ALTIUM_VALUE") "4.7uF")
        (field (name "TOLERANCE") "10%")
        (field (name "PART NUMBER") "GRM188R60J475KE19D")
        (field (name "MANUFACTURER") "Murata Electronics North America")
      )
      (libsource (lib "COMRAD_Database") (part "CAP_0603"))
    )
    (comp (ref "C101")
      (value "CAP_0603")
      (footprint "CAPC0603(1608)100_N:CAPC0603(1608)100_N")
      (description "4.7uF, ceramic, 10% 6.3V X5R Low ESR, 0603")
      (fields
        (field (name "ALTIUM_VALUE") "4.7uF")
        (field (name "TOLERANCE") "10%")
        (field (name "PART NUMBER") "GRM188R60J475KE19D")
        (field (name "MANUFACTURER") "Murata Electronics North America")
      )
      (libsource (lib "COMRAD_Database") (part "CAP_0603"))
    )
    (comp (ref "C102")
      (value "CAP_1206")
      (footprint "CAPC1206(3216)100_N:CAPC1206(3216)100_N")
      (description "CAP CER 100UF 6.3V 20% X5R 1206")
      (fields
        (field (name "ALTIUM_VALUE") "100uF")
        (field (name "TOLERANCE") "20%")
        (field (name "PART NUMBER") "JMK316BJ107ML-T")
        (field (name "MANUFACTURER") "Taiyo Yuden")
      )
      (libsource (lib "COMRAD_Database") (part "CAP_1206"))
    )
    (comp (ref "C103")
      (value "CAP_0402")
      (footprint "CAPC0402(1005)60_N:CAPC0402(1005)60_N")
      (description "10000pF, ceramic, 10% 6.3V X5R, 0402")
      (fields
        (field (name "ALTIUM_VALUE") "10nF")
        (field (name "TOLERANCE") "10%")
        (field (name "PART NUMBER") "GRM155R60J103KA01D")
        (field (name "MANUFACTURER") "Murata Electronics North America")
      )
      (libsource (lib "COMRAD_Database") (part "CAP_0402"))
    )
    (comp (ref "C104")
      (value "CAP_0402")
      (footprint "CAPC0402(1005)60_N:CAPC0402(1005)60_N")
      (description "10000pF, ceramic, 10% 6.3V X5R, 0402")
      (fields
        (field (name "ALTIUM_VALUE") "10nF")
        (field (name "TOLERANCE") "10%")
        (field (name "PART NUMBER") "GRM155R60J103KA01D")
        (field (name "MANUFACTURER") "Murata Electronics North America")
      )
      (libsource (lib "COMRAD_Database") (part "CAP_0402"))
    )
    (comp (ref "C105")
      (value "CAP_0402")
      (footprint "CAPC0402(1005)60_N:CAPC0402(1005)60_N")
      (description "0.047uF, ceramic, 10% 6.3V X5R, 0402")
      (fields
        (field (name "ALTIUM_VALUE") "47nF")
        (field (name "TOLERANCE") "10%")
        (field (name "PART NUMBER") "GRM155R60J473KA01D")
        (field (name "MANUFACTURER") "Murata Electronics North America")
      )
      (libsource (lib "COMRAD_Database") (part "CAP_0402"))
    )
    (comp (ref "C106")
      (value "CAP_0402")
      (footprint "CAPC0402(1005)60_N:CAPC0402(1005)60_N")
      (description "0.047uF, ceramic, 10% 6.3V X5R, 0402")
      (fields
        (field (name "ALTIUM_VALUE") "47nF")
        (field (name "TOLERANCE") "10%")
        (field (name "PART NUMBER") "GRM155R60J473KA01D")
        (field (name "MANUFACTURER") "Murata Electronics North America")
      )
      (libsource (lib "COMRAD_Database") (part "CAP_0402"))
    )
    (comp (ref "C107")
      (value "CAP_0402")
      (footprint "CAPC0402(1005)60_N:CAPC0402(1005)60_N")
      (description "0.047uF, ceramic, 10% 6.3V X5R, 0402")
      (fields
        (field (name "ALTIUM_VALUE") "47nF")
        (field (name "TOLERANCE") "10%")
        (field (name "PART NUMBER") "GRM155R60J473KA01D")
        (field (name "MANUFACTURER") "Murata Electronics North America")
      )
      (libsource (lib "COMRAD_Database") (part "CAP_0402"))
    )
    (comp (ref "C108")
      (value "CAP_0402")
      (footprint "CAPC0402(1005)60_N:CAPC0402(1005)60_N")
      (description "0.47uF, ceramic, 10% 6.3V X5R, 0402")
      (fields
        (field (name "ALTIUM_VALUE") "470nF")
        (field (name "TOLERANCE") "10%")
        (field (name "PART NUMBER") "GRM155R60J474KE19D")
        (field (name "MANUFACTURER") "Murata Electronics North America")
      )
      (libsource (lib "COMRAD_Database") (part "CAP_0402"))
    )
    (comp (ref "C109")
      (value "CAP_0402")
      (footprint "CAPC0402(1005)60_N:CAPC0402(1005)60_N")
      (description "10000pF, ceramic, 10% 6.3V X5R, 0402")
      (fields
        (field (name "ALTIUM_VALUE") "10nF")
        (field (name "TOLERANCE") "10%")
        (field (name "PART NUMBER") "GRM155R60J103KA01D")
        (field (name "MANUFACTURER") "Murata Electronics North America")
      )
      (libsource (lib "COMRAD_Database") (part "CAP_0402"))
    )
    (comp (ref "C110")
      (value "CAP_0402")
      (footprint "CAPC0402(1005)60_N:CAPC0402(1005)60_N")
      (description "10000pF, ceramic, 10% 6.3V X5R, 0402")
      (fields
        (field (name "ALTIUM_VALUE") "10nF")
        (field (name "TOLERANCE") "10%")
        (field (name "PART NUMBER") "GRM155R60J103KA01D")
        (field (name "MANUFACTURER") "Murata Electronics North America")
      )
      (libsource (lib "COMRAD_Database") (part "CAP_0402"))
    )
    (comp (ref "C111")
      (value "CAP_0603")
      (footprint "CAPC0603(1608)100_N:CAPC0603(1608)100_N")
      (description "4.7uF, ceramic, 10% 6.3V X5R Low ESR, 0603")
      (fields
        (field (name "ALTIUM_VALUE") "4.7uF")
        (field (name "TOLERANCE") "10%")
        (field (name "PART NUMBER") "GRM188R60J475KE19D")
        (field (name "MANUFACTURER") "Murata Electronics North America")
      )
      (libsource (lib "COMRAD_Database") (part "CAP_0603"))
    )
    (comp (ref "C112")
      (value "CAP_0603")
      (footprint "CAPC0603(1608)100_N:CAPC0603(1608)100_N")
      (description "4.7uF, ceramic, 10% 6.3V X5R Low ESR, 0603")
      (fields
        (field (name "ALTIUM_VALUE") "4.7uF")
        (field (name "TOLERANCE") "10%")
        (field (name "PART NUMBER") "GRM188R60J475KE19D")
        (field (name "MANUFACTURER") "Murata Electronics North America")
      )
      (libsource (lib "COMRAD_Database") (part "CAP_0603"))
    )
    (comp (ref "C113")
      (value "CAP_1206")
      (footprint "CAPC1206(3216)100_N:CAPC1206(3216)100_N")
      (description "CAP CER 100UF 6.3V 20% X5R 1206")
      (fields
        (field (name "ALTIUM_VALUE") "100uF")
        (field (name "TOLERANCE") "20%")
        (field (name "PART NUMBER") "JMK316BJ107ML-T")
        (field (name "MANUFACTURER") "Taiyo Yuden")
      )
      (libsource (lib "COMRAD_Database") (part "CAP_1206"))
    )
    (comp (ref "C114")
      (value "CAP_0402")
      (footprint "CAPC0402(1005)60_N:CAPC0402(1005)60_N")
      (description "10000pF, ceramic, 10% 6.3V X5R, 0402")
      (fields
        (field (name "ALTIUM_VALUE") "10nF")
        (field (name "TOLERANCE") "10%")
        (field (name "PART NUMBER") "GRM155R60J103KA01D")
        (field (name "MANUFACTURER") "Murata Electronics North America")
      )
      (libsource (lib "COMRAD_Database") (part "CAP_0402"))
    )
    (comp (ref "C115")
      (value "CAP_0402")
      (footprint "CAPC0402(1005)60_N:CAPC0402(1005)60_N")
      (description "10000pF, ceramic, 10% 6.3V X5R, 0402")
      (fields
        (field (name "ALTIUM_VALUE") "10nF")
        (field (name "TOLERANCE") "10%")
        (field (name "PART NUMBER") "GRM155R60J103KA01D")
        (field (name "MANUFACTURER") "Murata Electronics North America")
      )
      (libsource (lib "COMRAD_Database") (part "CAP_0402"))
    )
    (comp (ref "C116")
      (value "CAP_0402")
      (footprint "CAPC0402(1005)60_N:CAPC0402(1005)60_N")
      (description "0.047uF, ceramic, 10% 6.3V X5R, 0402")
      (fields
        (field (name "ALTIUM_VALUE") "47nF")
        (field (name "TOLERANCE") "10%")
        (field (name "PART NUMBER") "GRM155R60J473KA01D")
        (field (name "MANUFACTURER") "Murata Electronics North America")
      )
      (libsource (lib "COMRAD_Database") (part "CAP_0402"))
    )
    (comp (ref "C117")
      (value "CAP_0402")
      (footprint "CAPC0402(1005)60_N:CAPC0402(1005)60_N")
      (description "0.047uF, ceramic, 10% 6.3V X5R, 0402")
      (fields
        (field (name "ALTIUM_VALUE") "47nF")
        (field (name "TOLERANCE") "10%")
        (field (name "PART NUMBER") "GRM155R60J473KA01D")
        (field (name "MANUFACTURER") "Murata Electronics North America")
      )
      (libsource (lib "COMRAD_Database") (part "CAP_0402"))
    )
    (comp (ref "C118")
      (value "CAP_0402")
      (footprint "CAPC0402(1005)60_N:CAPC0402(1005)60_N")
      (description "0.047uF, ceramic, 10% 6.3V X5R, 0402")
      (fields
        (field (name "ALTIUM_VALUE") "47nF")
        (field (name "TOLERANCE") "10%")
        (field (name "PART NUMBER") "GRM155R60J473KA01D")
        (field (name "MANUFACTURER") "Murata Electronics North America")
      )
      (libsource (lib "COMRAD_Database") (part "CAP_0402"))
    )
    (comp (ref "C119")
      (value "CAP_0402")
      (footprint "CAPC0402(1005)60_N:CAPC0402(1005)60_N")
      (description "0.47uF, ceramic, 10% 6.3V X5R, 0402")
      (fields
        (field (name "ALTIUM_VALUE") "470nF")
        (field (name "TOLERANCE") "10%")
        (field (name "PART NUMBER") "GRM155R60J474KE19D")
        (field (name "MANUFACTURER") "Murata Electronics North America")
      )
      (libsource (lib "COMRAD_Database") (part "CAP_0402"))
    )
    (comp (ref "C120")
      (value "0.1uF")
      (footprint "CAPC0402(1005)60_N")
      (description "0.1uF, ceramic, 10%, 25V, X5R, 0402")
      (fields (field (name "TOLERANCE") "10%") (field (name "PART NUMBER") "TMK105BJ104KV-F"))
      (libsource (lib "COMRAD_Database") (part "CAP_0402"))
    )
    (comp (ref "C121")
      (value "0.1uF")
      (footprint "CAPC0402(1005)60_N")
      (description "0.1uF, ceramic, 10%, 25V, X5R, 0402")
      (fields (field (name "TOLERANCE") "10%") (field (name "PART NUMBER") "TMK105BJ104KV-F"))
      (libsource (lib "COMRAD_Database") (part "CAP_0402"))
    )
    (comp (ref "C122")
      (value "CAP_0402")
      (footprint "CAPC0402(1005)60_N:CAPC0402(1005)60_N")
      (description "0.047uF, ceramic, 10% 6.3V X5R, 0402")
      (fields
        (field (name "ALTIUM_VALUE") "47nF")
        (field (name "TOLERANCE") "10%")
        (field (name "PART NUMBER") "GRM155R60J473KA01D")
        (field (name "MANUFACTURER") "Murata Electronics North America")
      )
      (libsource (lib "COMRAD_Database") (part "CAP_0402"))
    )
    (comp (ref "C123")
      (value "CAP_0402")
      (footprint "CAPC0402(1005)60_N:CAPC0402(1005)60_N")
      (description "0.047uF, ceramic, 10% 6.3V X5R, 0402")
      (fields
        (field (name "ALTIUM_VALUE") "47nF")
        (field (name "TOLERANCE") "10%")
        (field (name "PART NUMBER") "GRM155R60J473KA01D")
        (field (name "MANUFACTURER") "Murata Electronics North America")
      )
      (libsource (lib "COMRAD_Database") (part "CAP_0402"))
    )
    (comp (ref "C124")
      (value "CAP_0402")
      (footprint "CAPC0402(1005)60_N:CAPC0402(1005)60_N")
      (description "0.047uF, ceramic, 10% 6.3V X5R, 0402")
      (fields
        (field (name "ALTIUM_VALUE") "47nF")
        (field (name "TOLERANCE") "10%")
        (field (name "PART NUMBER") "GRM155R60J473KA01D")
        (field (name "MANUFACTURER") "Murata Electronics North America")
      )
      (libsource (lib "COMRAD_Database") (part "CAP_0402"))
    )
    (comp (ref "C125")
      (value "CAP_0402")
      (footprint "CAPC0402(1005)60_N:CAPC0402(1005)60_N")
      (description "0.047uF, ceramic, 10% 6.3V X5R, 0402")
      (fields
        (field (name "ALTIUM_VALUE") "47nF")
        (field (name "TOLERANCE") "10%")
        (field (name "PART NUMBER") "GRM155R60J473KA01D")
        (field (name "MANUFACTURER") "Murata Electronics North America")
      )
      (libsource (lib "COMRAD_Database") (part "CAP_0402"))
    )
    (comp (ref "C126")
      (value "CAP_0402")
      (footprint "CAPC0402(1005)60_N:CAPC0402(1005)60_N")
      (description "0.047uF, ceramic, 10% 6.3V X5R, 0402")
      (fields
        (field (name "ALTIUM_VALUE") "47nF")
        (field (name "TOLERANCE") "10%")
        (field (name "PART NUMBER") "GRM155R60J473KA01D")
        (field (name "MANUFACTURER") "Murata Electronics North America")
      )
      (libsource (lib "COMRAD_Database") (part "CAP_0402"))
    )
    (comp (ref "C127")
      (value "CAP_0402")
      (footprint "CAPC0402(1005)60_N:CAPC0402(1005)60_N")
      (description "0.047uF, ceramic, 10% 6.3V X5R, 0402")
      (fields
        (field (name "ALTIUM_VALUE") "47nF")
        (field (name "TOLERANCE") "10%")
        (field (name "PART NUMBER") "GRM155R60J473KA01D")
        (field (name "MANUFACTURER") "Murata Electronics North America")
      )
      (libsource (lib "COMRAD_Database") (part "CAP_0402"))
    )
    (comp (ref "C128")
      (value "CAP_0402")
      (footprint "CAPC0402(1005)60_N:CAPC0402(1005)60_N")
      (description "0.047uF, ceramic, 10% 6.3V X5R, 0402")
      (fields
        (field (name "ALTIUM_VALUE") "47nF")
        (field (name "TOLERANCE") "10%")
        (field (name "PART NUMBER") "GRM155R60J473KA01D")
        (field (name "MANUFACTURER") "Murata Electronics North America")
      )
      (libsource (lib "COMRAD_Database") (part "CAP_0402"))
    )
    (comp (ref "C129")
      (value "CAP_0402")
      (footprint "CAPC0402(1005)60_N:CAPC0402(1005)60_N")
      (description "10000pF, ceramic, 10% 6.3V X5R, 0402")
      (fields
        (field (name "ALTIUM_VALUE") "10nF")
        (field (name "TOLERANCE") "10%")
        (field (name "PART NUMBER") "GRM155R60J103KA01D")
        (field (name "MANUFACTURER") "Murata Electronics North America")
      )
      (libsource (lib "COMRAD_Database") (part "CAP_0402"))
    )
    (comp (ref "C130")
      (value "CAP_0402")
      (footprint "CAPC0402(1005)60_N:CAPC0402(1005)60_N")
      (description "10000pF, ceramic, 10% 6.3V X5R, 0402")
      (fields
        (field (name "ALTIUM_VALUE") "10nF")
        (field (name "TOLERANCE") "10%")
        (field (name "PART NUMBER") "GRM155R60J103KA01D")
        (field (name "MANUFACTURER") "Murata Electronics North America")
      )
      (libsource (lib "COMRAD_Database") (part "CAP_0402"))
    )
    (comp (ref "C131")
      (value "CAP_0402")
      (footprint "CAPC0402(1005)60_N:CAPC0402(1005)60_N")
      (description "10000pF, ceramic, 10% 6.3V X5R, 0402")
      (fields
        (field (name "ALTIUM_VALUE") "10nF")
        (field (name "TOLERANCE") "10%")
        (field (name "PART NUMBER") "GRM155R60J103KA01D")
        (field (name "MANUFACTURER") "Murata Electronics North America")
      )
      (libsource (lib "COMRAD_Database") (part "CAP_0402"))
    )
    (comp (ref "C132")
      (value "CAP_0402")
      (footprint "CAPC0402(1005)60_N:CAPC0402(1005)60_N")
      (description "10000pF, ceramic, 10% 6.3V X5R, 0402")
      (fields
        (field (name "ALTIUM_VALUE") "10nF")
        (field (name "TOLERANCE") "10%")
        (field (name "PART NUMBER") "GRM155R60J103KA01D")
        (field (name "MANUFACTURER") "Murata Electronics North America")
      )
      (libsource (lib "COMRAD_Database") (part "CAP_0402"))
    )
    (comp (ref "C133")
      (value "CAP_0402")
      (footprint "CAPC0402(1005)60_N:CAPC0402(1005)60_N")
      (description "10000pF, ceramic, 10% 6.3V X5R, 0402")
      (fields
        (field (name "ALTIUM_VALUE") "10nF")
        (field (name "TOLERANCE") "10%")
        (field (name "PART NUMBER") "GRM155R60J103KA01D")
        (field (name "MANUFACTURER") "Murata Electronics North America")
      )
      (libsource (lib "COMRAD_Database") (part "CAP_0402"))
    )
    (comp (ref "C134")
      (value "CAP_0402")
      (footprint "CAPC0402(1005)60_N:CAPC0402(1005)60_N")
      (description "0.047uF, ceramic, 10% 6.3V X5R, 0402")
      (fields
        (field (name "ALTIUM_VALUE") "47nF")
        (field (name "TOLERANCE") "10%")
        (field (name "PART NUMBER") "GRM155R60J473KA01D")
        (field (name "MANUFACTURER") "Murata Electronics North America")
      )
      (libsource (lib "COMRAD_Database") (part "CAP_0402"))
    )
    (comp (ref "C135")
      (value "CAP_0402")
      (footprint "CAPC0402(1005)60_N:CAPC0402(1005)60_N")
      (description "0.047uF, ceramic, 10% 6.3V X5R, 0402")
      (fields
        (field (name "ALTIUM_VALUE") "47nF")
        (field (name "TOLERANCE") "10%")
        (field (name "PART NUMBER") "GRM155R60J473KA01D")
        (field (name "MANUFACTURER") "Murata Electronics North America")
      )
      (libsource (lib "COMRAD_Database") (part "CAP_0402"))
    )
    (comp (ref "C136")
      (value "CAP_0402")
      (footprint "CAPC0402(1005)60_N:CAPC0402(1005)60_N")
      (description "0.047uF, ceramic, 10% 6.3V X5R, 0402")
      (fields
        (field (name "ALTIUM_VALUE") "47nF")
        (field (name "TOLERANCE") "10%")
        (field (name "PART NUMBER") "GRM155R60J473KA01D")
        (field (name "MANUFACTURER") "Murata Electronics North America")
      )
      (libsource (lib "COMRAD_Database") (part "CAP_0402"))
    )
    (comp (ref "C137")
      (value "CAP_0402")
      (footprint "CAPC0402(1005)60_N:CAPC0402(1005)60_N")
      (description "0.047uF, ceramic, 10% 6.3V X5R, 0402")
      (fields
        (field (name "ALTIUM_VALUE") "47nF")
        (field (name "TOLERANCE") "10%")
        (field (name "PART NUMBER") "GRM155R60J473KA01D")
        (field (name "MANUFACTURER") "Murata Electronics North America")
      )
      (libsource (lib "COMRAD_Database") (part "CAP_0402"))
    )
    (comp (ref "C138")
      (value "CAP_0402")
      (footprint "CAPC0402(1005)60_N:CAPC0402(1005)60_N")
      (description "0.047uF, ceramic, 10% 6.3V X5R, 0402")
      (fields
        (field (name "ALTIUM_VALUE") "47nF")
        (field (name "TOLERANCE") "10%")
        (field (name "PART NUMBER") "GRM155R60J473KA01D")
        (field (name "MANUFACTURER") "Murata Electronics North America")
      )
      (libsource (lib "COMRAD_Database") (part "CAP_0402"))
    )
    (comp (ref "C139")
      (value "CAP_0402")
      (footprint "CAPC0402(1005)60_N:CAPC0402(1005)60_N")
      (description "0.047uF, ceramic, 10% 6.3V X5R, 0402")
      (fields
        (field (name "ALTIUM_VALUE") "47nF")
        (field (name "TOLERANCE") "10%")
        (field (name "PART NUMBER") "GRM155R60J473KA01D")
        (field (name "MANUFACTURER") "Murata Electronics North America")
      )
      (libsource (lib "COMRAD_Database") (part "CAP_0402"))
    )
    (comp (ref "C140")
      (value "CAP_1206")
      (footprint "CAPC1206(3216)100_N:CAPC1206(3216)100_N")
      (description "CAP CER 100UF 6.3V 20% X5R 1206")
      (fields
        (field (name "ALTIUM_VALUE") "100uF")
        (field (name "TOLERANCE") "20%")
        (field (name "PART NUMBER") "JMK316BJ107ML-T")
        (field (name "MANUFACTURER") "Taiyo Yuden")
      )
      (libsource (lib "COMRAD_Database") (part "CAP_1206"))
    )
    (comp (ref "C141")
      (value "CAP_1206")
      (footprint "CAPC1206(3216)100_N:CAPC1206(3216)100_N")
      (description "CAP CER 100UF 6.3V 20% X5R 1206")
      (fields
        (field (name "ALTIUM_VALUE") "100uF")
        (field (name "TOLERANCE") "20%")
        (field (name "PART NUMBER") "JMK316BJ107ML-T")
        (field (name "MANUFACTURER") "Taiyo Yuden")
      )
      (libsource (lib "COMRAD_Database") (part "CAP_1206"))
    )
    (comp (ref "C142")
      (value "CAP_1206")
      (footprint "CAPC1206(3216)100_N:CAPC1206(3216)100_N")
      (description "CAP CER 100UF 6.3V 20% X5R 1206")
      (fields
        (field (name "ALTIUM_VALUE") "100uF")
        (field (name "TOLERANCE") "20%")
        (field (name "PART NUMBER") "JMK316BJ107ML-T")
        (field (name "MANUFACTURER") "Taiyo Yuden")
      )
      (libsource (lib "COMRAD_Database") (part "CAP_1206"))
    )
    (comp (ref "C143")
      (value "CAP_0603")
      (footprint "CAPC0603(1608)100_N:CAPC0603(1608)100_N")
      (description "4.7uF, ceramic, 10% 6.3V X5R Low ESR, 0603")
      (fields
        (field (name "ALTIUM_VALUE") "4.7uF")
        (field (name "TOLERANCE") "10%")
        (field (name "PART NUMBER") "GRM188R60J475KE19D")
        (field (name "MANUFACTURER") "Murata Electronics North America")
      )
      (libsource (lib "COMRAD_Database") (part "CAP_0603"))
    )
    (comp (ref "C144")
      (value "CAP_0603")
      (footprint "CAPC0603(1608)100_N:CAPC0603(1608)100_N")
      (description "4.7uF, ceramic, 10% 6.3V X5R Low ESR, 0603")
      (fields
        (field (name "ALTIUM_VALUE") "4.7uF")
        (field (name "TOLERANCE") "10%")
        (field (name "PART NUMBER") "GRM188R60J475KE19D")
        (field (name "MANUFACTURER") "Murata Electronics North America")
      )
      (libsource (lib "COMRAD_Database") (part "CAP_0603"))
    )
    (comp (ref "C145")
      (value "CAP_0603")
      (footprint "CAPC0603(1608)100_N:CAPC0603(1608)100_N")
      (description "4.7uF, ceramic, 10% 6.3V X5R Low ESR, 0603")
      (fields
        (field (name "ALTIUM_VALUE") "4.7uF")
        (field (name "TOLERANCE") "10%")
        (field (name "PART NUMBER") "GRM188R60J475KE19D")
        (field (name "MANUFACTURER") "Murata Electronics North America")
      )
      (libsource (lib "COMRAD_Database") (part "CAP_0603"))
    )
    (comp (ref "C146")
      (value "CAP_0603")
      (footprint "CAPC0603(1608)100_N:CAPC0603(1608)100_N")
      (description "4.7uF, ceramic, 10% 6.3V X5R Low ESR, 0603")
      (fields
        (field (name "ALTIUM_VALUE") "4.7uF")
        (field (name "TOLERANCE") "10%")
        (field (name "PART NUMBER") "GRM188R60J475KE19D")
        (field (name "MANUFACTURER") "Murata Electronics North America")
      )
      (libsource (lib "COMRAD_Database") (part "CAP_0603"))
    )
    (comp (ref "C147")
      (value "CAP_0603")
      (footprint "CAPC0603(1608)100_N:CAPC0603(1608)100_N")
      (description "4.7uF, ceramic, 10% 6.3V X5R Low ESR, 0603")
      (fields
        (field (name "ALTIUM_VALUE") "4.7uF")
        (field (name "TOLERANCE") "10%")
        (field (name "PART NUMBER") "GRM188R60J475KE19D")
        (field (name "MANUFACTURER") "Murata Electronics North America")
      )
      (libsource (lib "COMRAD_Database") (part "CAP_0603"))
    )
    (comp (ref "C148")
      (value "CAP_0402")
      (footprint "CAPC0402(1005)60_N:CAPC0402(1005)60_N")
      (description "0.47uF, ceramic, 10% 6.3V X5R, 0402")
      (fields
        (field (name "ALTIUM_VALUE") "470nF")
        (field (name "TOLERANCE") "10%")
        (field (name "PART NUMBER") "GRM155R60J474KE19D")
        (field (name "MANUFACTURER") "Murata Electronics North America")
      )
      (libsource (lib "COMRAD_Database") (part "CAP_0402"))
    )
    (comp (ref "C149")
      (value "0.1uF")
      (footprint "CAPC0402(1005)60_N")
      (description "0.1uF, ceramic, 10%, 25V, X5R, 0402")
      (fields (field (name "TOLERANCE") "10%") (field (name "PART NUMBER") "TMK105BJ104KV-F"))
      (libsource (lib "COMRAD_Database") (part "CAP_0402"))
    )
    (comp (ref "C150")
      (value "0.1uF")
      (footprint "CAPC0402(1005)60_N")
      (description "0.1uF, ceramic, 10%, 25V, X5R, 0402")
      (fields (field (name "TOLERANCE") "10%") (field (name "PART NUMBER") "TMK105BJ104KV-F"))
      (libsource (lib "COMRAD_Database") (part "CAP_0402"))
    )
    (comp (ref "C151")
      (value "CAP_0603")
      (footprint "CAPC0603(1608)100_N:CAPC0603(1608)100_N")
      (description "4.7uF, ceramic, 10% 6.3V X5R Low ESR, 0603")
      (fields
        (field (name "ALTIUM_VALUE") "4.7uF")
        (field (name "TOLERANCE") "10%")
        (field (name "PART NUMBER") "GRM188R60J475KE19D")
        (field (name "MANUFACTURER") "Murata Electronics North America")
      )
      (libsource (lib "COMRAD_Database") (part "CAP_0603"))
    )
    (comp (ref "C152")
      (value "CAP_0603")
      (footprint "CAPC0603(1608)100_N:CAPC0603(1608)100_N")
      (description "4.7uF, ceramic, 10% 6.3V X5R Low ESR, 0603")
      (fields
        (field (name "ALTIUM_VALUE") "4.7uF")
        (field (name "TOLERANCE") "10%")
        (field (name "PART NUMBER") "GRM188R60J475KE19D")
        (field (name "MANUFACTURER") "Murata Electronics North America")
      )
      (libsource (lib "COMRAD_Database") (part "CAP_0603"))
    )
    (comp (ref "C153")
      (value "CAP_0603")
      (footprint "CAPC0603(1608)100_N:CAPC0603(1608)100_N")
      (description "4.7uF, ceramic, 10% 6.3V X5R Low ESR, 0603")
      (fields
        (field (name "ALTIUM_VALUE") "4.7uF")
        (field (name "TOLERANCE") "10%")
        (field (name "PART NUMBER") "GRM188R60J475KE19D")
        (field (name "MANUFACTURER") "Murata Electronics North America")
      )
      (libsource (lib "COMRAD_Database") (part "CAP_0603"))
    )
    (comp (ref "C154")
      (value "CAP_1206")
      (footprint "CAPC1206(3216)100_N:CAPC1206(3216)100_N")
      (description "CAP CER 100UF 6.3V 20% X5R 1206")
      (fields
        (field (name "ALTIUM_VALUE") "100uF")
        (field (name "TOLERANCE") "20%")
        (field (name "PART NUMBER") "JMK316BJ107ML-T")
        (field (name "MANUFACTURER") "Taiyo Yuden")
      )
      (libsource (lib "COMRAD_Database") (part "CAP_1206"))
    )
    (comp (ref "C155")
      (value "CAP_0402")
      (footprint "CAPC0402(1005)60_N:CAPC0402(1005)60_N")
      (description "0.47uF, ceramic, 10% 6.3V X5R, 0402")
      (fields
        (field (name "ALTIUM_VALUE") "470nF")
        (field (name "TOLERANCE") "10%")
        (field (name "PART NUMBER") "GRM155R60J474KE19D")
        (field (name "MANUFACTURER") "Murata Electronics North America")
      )
      (libsource (lib "COMRAD_Database") (part "CAP_0402"))
    )
    (comp (ref "C156")
      (value "CAP_0603")
      (footprint "CAPC0402(1005)60_N")
      (description "10000pF, ceramic, 10% 6.3V X5R, 0402")
      (fields
        (field (name "ALTIUM_VALUE") "10nF")
        (field (name "TOLERANCE") "20%")
        (field (name "PART NUMBER") "GRM155R60J103KA01D")
        (field (name "MANUFACTURER") "Murata Electronics North America")
      )
      (libsource (lib "COMRAD_Database") (part "CAP_0603"))
    )
    (comp (ref "FB1")
      (value "FB0805")
      (footprint "Inductor0805(2012)")
      (description "MPZ2012S601A, 600 ohm, 100MHz, 0805")
      (fields
        (field (name "RESISTANCE") "600")
        (field (name "MAX_CURRENT") "*")
        (field (name "PART NUMBER") "MPZ2012S601A")
        (field (name "MANUFACTURER") "TDK Corporation")
      )
      (libsource (lib "COMRAD_Database") (part "FerriteBead0805"))
    )
    (comp (ref "U2")
      (value "XC7Z020-1CLG484CES")
      (footprint "ZYNQ_xc7z020clg484pkg_BGA-484")
      (description "XC7Z020-1CLG484CES, Zynq-7000 All Programmable SoC")
      (fields (field (name "MANUFACTURER") "Xilinx"))
      (libsource (lib "") (part "ZYNQ_XC7Z020CLG484PKG_1"))
    )
  )
  (nets
    (net (code "1") (name "/VCC_PLL") (class "Default")
      (node (ref "C156") (pin "2") (pinfunction "2_2") (pintype "passive"))
      (node (ref "FB1") (pin "1") (pinfunction "1_1") (pintype "passive"))
      (node (ref "U2") (pin "H10") (pinfunction "VCCPLL_H10") (pintype "power_in"))
    )
    (net (code "2") (name "DDR_1V5") (class "Default")
      (node (ref "C28") (pin "2") (pinfunction "2_2") (pintype "passive"))
      (node (ref "C29") (pin "2") (pinfunction "2_2") (pintype "passive"))
      (node (ref "C30") (pin "2") (pinfunction "2_2") (pintype "passive"))
      (node (ref "C31") (pin "2") (pinfunction "2_2") (pintype "passive"))
      (node (ref "C32") (pin "2") (pinfunction "2_2") (pintype "passive"))
      (node (ref "C33") (pin "2") (pinfunction "2_2") (pintype "passive"))
      (node (ref "C34") (pin "2") (pinfunction "2_2") (pintype "passive"))
      (node (ref "C35") (pin "2") (pinfunction "2_2") (pintype "passive"))
      (node (ref "C36") (pin "2") (pinfunction "2_2") (pintype "passive"))
      (node (ref "C37") (pin "2") (pinfunction "2_2") (pintype "passive"))
      (node (ref "C38") (pin "2") (pinfunction "2_2") (pintype "passive"))
      (node (ref "C52") (pin "2") (pinfunction "2_2") (pintype "passive"))
      (node (ref "C53") (pin "2") (pinfunction "2_2") (pintype "passive"))
      (node (ref "C54") (pin "2") (pinfunction "2_2") (pintype "passive"))
      (node (ref "C55") (pin "2") (pinfunction "2_2") (pintype "passive"))
      (node (ref "C56") (pin "2") (pinfunction "2_2") (pintype "passive"))
      (node (ref "C57") (pin "2") (pinfunction "2_2") (pintype "passive"))
      (node (ref "C58") (pin "2") (pinfunction "2_2") (pintype "passive"))
      (node (ref "U2") (pin "E2") (pinfunction "VCCO_DDR_502_E2") (pintype "power_in"))
      (node (ref "U2") (pin "F5") (pinfunction "VCCO_DDR_502_F5") (pintype "power_in"))
      (node (ref "U2") (pin "H1") (pinfunction "VCCO_DDR_502_H1") (pintype "power_in"))
      (node (ref "U2") (pin "J4") (pinfunction "VCCO_DDR_502_J4") (pintype "power_in"))
      (node (ref "U2") (pin "K7") (pinfunction "VCCO_DDR_502_K7") (pintype "power_in"))
      (node (ref "U2") (pin "M3") (pinfunction "VCCO_DDR_502_M3") (pintype "power_in"))
      (node (ref "U2") (pin "N6") (pinfunction "VCCO_DDR_502_N6") (pintype "power_in"))
      (node (ref "U2") (pin "R2") (pinfunction "VCCO_DDR_502_R2") (pintype "power_in"))
      (node (ref "U2") (pin "V1") (pinfunction "VCCO_DDR_502_V1") (pintype "power_in"))
    )
    (net (code "3") (name "DDR_VREF") (class "Default")
      (node (ref "C109") (pin "2") (pinfunction "2_2") (pintype "passive"))
      (node (ref "C110") (pin "2") (pinfunction "2_2") (pintype "passive"))
      (node (ref "U2") (pin "H7") (pinfunction "PS_DDR_VREF0_502_H7") (pintype "power_in"))
      (node (ref "U2") (pin "P7") (pinfunction "PS_DDR_VREF1_502_P7") (pintype "power_in"))
    )
    (net (code "4") (name "GND") (class "Default")
      (node (ref "C10") (pin "1") (pinfunction "1_1") (pintype "passive"))
      (node (ref "C100") (pin "1") (pinfunction "1_1") (pintype "passive"))
      (node (ref "C101") (pin "1") (pinfunction "1_1") (pintype "passive"))
      (node (ref "C102") (pin "1") (pinfunction "1_1") (pintype "passive"))
      (node (ref "C103") (pin "1") (pinfunction "1_1") (pintype "passive"))
      (node (ref "C104") (pin "1") (pinfunction "1_1") (pintype "passive"))
      (node (ref "C105") (pin "1") (pinfunction "1_1") (pintype "passive"))
      (node (ref "C106") (pin "1") (pinfunction "1_1") (pintype "passive"))
      (node (ref "C107") (pin "1") (pinfunction "1_1") (pintype "passive"))
      (node (ref "C108") (pin "1") (pinfunction "1_1") (pintype "passive"))
      (node (ref "C109") (pin "1") (pinfunction "1_1") (pintype "passive"))
      (node (ref "C11") (pin "1") (pinfunction "1_1") (pintype "passive"))
      (node (ref "C110") (pin "1") (pinfunction "1_1") (pintype "passive"))
      (node (ref "C111") (pin "1") (pinfunction "1_1") (pintype "passive"))
      (node (ref "C112") (pin "1") (pinfunction "1_1") (pintype "passive"))
      (node (ref "C113") (pin "1") (pinfunction "1_1") (pintype "passive"))
      (node (ref "C114") (pin "1") (pinfunction "1_1") (pintype "passive"))
      (node (ref "C115") (pin "1") (pinfunction "1_1") (pintype "passive"))
      (node (ref "C116") (pin "1") (pinfunction "1_1") (pintype "passive"))
      (node (ref "C117") (pin "1") (pinfunction "1_1") (pintype "passive"))
      (node (ref "C118") (pin "1") (pinfunction "1_1") (pintype "passive"))
      (node (ref "C119") (pin "1") (pinfunction "1_1") (pintype "passive"))
      (node (ref "C12") (pin "1") (pinfunction "1_1") (pintype "passive"))
      (node (ref "C120") (pin "1") (pinfunction "1_1") (pintype "passive"))
      (node (ref "C121") (pin "1") (pinfunction "1_1") (pintype "passive"))
      (node (ref "C122") (pin "1") (pinfunction "1_1") (pintype "passive"))
      (node (ref "C123") (pin "1") (pinfunction "1_1") (pintype "passive"))
      (node (ref "C124") (pin "1") (pinfunction "1_1") (pintype "passive"))
      (node (ref "C125") (pin "1") (pinfunction "1_1") (pintype "passive"))
      (node (ref "C126") (pin "1") (pinfunction "1_1") (pintype "passive"))
      (node (ref "C127") (pin "1") (pinfunction "1_1") (pintype "passive"))
      (node (ref "C128") (pin "1") (pinfunction "1_1") (pintype "passive"))
      (node (ref "C129") (pin "1") (pinfunction "1_1") (pintype "passive"))
      (node (ref "C13") (pin "1") (pinfunction "1_1") (pintype "passive"))
      (node (ref "C130") (pin "1") (pinfunction "1_1") (pintype "passive"))
      (node (ref "C131") (pin "1") (pinfunction "1_1") (pintype "passive"))
      (node (ref "C132") (pin "1") (pinfunction "1_1") (pintype "passive"))
      (node (ref "C133") (pin "1") (pinfunction "1_1") (pintype "passive"))
      (node (ref "C134") (pin "1") (pinfunction "1_1") (pintype "passive"))
      (node (ref "C135") (pin "1") (pinfunction "1_1") (pintype "passive"))
      (node (ref "C136") (pin "1") (pinfunction "1_1") (pintype "passive"))
      (node (ref "C137") (pin "1") (pinfunction "1_1") (pintype "passive"))
      (node (ref "C138") (pin "1") (pinfunction "1_1") (pintype "passive"))
      (node (ref "C139") (pin "1") (pinfunction "1_1") (pintype "passive"))
      (node (ref "C14") (pin "1") (pinfunction "1_1") (pintype "passive"))
      (node (ref "C140") (pin "1") (pinfunction "1_1") (pintype "passive"))
      (node (ref "C141") (pin "1") (pinfunction "1_1") (pintype "passive"))
      (node (ref "C142") (pin "1") (pinfunction "1_1") (pintype "passive"))
      (node (ref "C143") (pin "1") (pinfunction "1_1") (pintype "passive"))
      (node (ref "C144") (pin "1") (pinfunction "1_1") (pintype "passive"))
      (node (ref "C145") (pin "1") (pinfunction "1_1") (pintype "passive"))
      (node (ref "C146") (pin "1") (pinfunction "1_1") (pintype "passive"))
      (node (ref "C147") (pin "1") (pinfunction "1_1") (pintype "passive"))
      (node (ref "C148") (pin "1") (pinfunction "1_1") (pintype "passive"))
      (node (ref "C149") (pin "1") (pinfunction "1_1") (pintype "passive"))
      (node (ref "C15") (pin "1") (pinfunction "1_1") (pintype "passive"))
      (node (ref "C150") (pin "1") (pinfunction "1_1") (pintype "passive"))
      (node (ref "C151") (pin "1") (pinfunction "1_1") (pintype "passive"))
      (node (ref "C152") (pin "1") (pinfunction "1_1") (pintype "passive"))
      (node (ref "C153") (pin "1") (pinfunction "1_1") (pintype "passive"))
      (node (ref "C154") (pin "1") (pinfunction "1_1") (pintype "passive"))
      (node (ref "C155") (pin "1") (pinfunction "1_1") (pintype "passive"))
      (node (ref "C156") (pin "1") (pinfunction "1_1") (pintype "passive"))
      (node (ref "C16") (pin "1") (pinfunction "1_1") (pintype "passive"))
      (node (ref "C17") (pin "1") (pinfunction "1_1") (pintype "passive"))
      (node (ref "C18") (pin "1") (pinfunction "1_1") (pintype "passive"))
      (node (ref "C19") (pin "1") (pinfunction "1_1") (pintype "passive"))
      (node (ref "C20") (pin "1") (pinfunction "1_1") (pintype "passive"))
      (node (ref "C21") (pin "1") (pinfunction "1_1") (pintype "passive"))
      (node (ref "C22") (pin "1") (pinfunction "1_1") (pintype "passive"))
      (node (ref "C23") (pin "1") (pinfunction "1_1") (pintype "passive"))
      (node (ref "C24") (pin "1") (pinfunction "1_1") (pintype "passive"))
      (node (ref "C25") (pin "1") (pinfunction "1_1") (pintype "passive"))
      (node (ref "C26") (pin "1") (pinfunction "1_1") (pintype "passive"))
      (node (ref "C27") (pin "1") (pinfunction "1_1") (pintype "passive"))
      (node (ref "C28") (pin "1") (pinfunction "1_1") (pintype "passive"))
      (node (ref "C29") (pin "1") (pinfunction "1_1") (pintype "passive"))
      (node (ref "C30") (pin "1") (pinfunction "1_1") (pintype "passive"))
      (node (ref "C31") (pin "1") (pinfunction "1_1") (pintype "passive"))
      (node (ref "C32") (pin "1") (pinfunction "1_1") (pintype "passive"))
      (node (ref "C33") (pin "1") (pinfunction "1_1") (pintype "passive"))
      (node (ref "C34") (pin "1") (pinfunction "1_1") (pintype "passive"))
      (node (ref "C35") (pin "1") (pinfunction "1_1") (pintype "passive"))
      (node (ref "C36") (pin "1") (pinfunction "1_1") (pintype "passive"))
      (node (ref "C37") (pin "1") (pinfunction "1_1") (pintype "passive"))
      (node (ref "C38") (pin "1") (pinfunction "1_1") (pintype "passive"))
      (node (ref "C39") (pin "1") (pinfunction "1_1") (pintype "passive"))
      (node (ref "C40") (pin "1") (pinfunction "1_1") (pintype "passive"))
      (node (ref "C41") (pin "1") (pinfunction "1_1") (pintype "passive"))
      (node (ref "C42") (pin "1") (pinfunction "1_1") (pintype "passive"))
      (node (ref "C43") (pin "1") (pinfunction "1_1") (pintype "passive"))
      (node (ref "C44") (pin "1") (pinfunction "1_1") (pintype "passive"))
      (node (ref "C45") (pin "1") (pinfunction "1_1") (pintype "passive"))
      (node (ref "C46") (pin "1") (pinfunction "1_1") (pintype "passive"))
      (node (ref "C47") (pin "1") (pinfunction "1_1") (pintype "passive"))
      (node (ref "C48") (pin "1") (pinfunction "1_1") (pintype "passive"))
      (node (ref "C49") (pin "1") (pinfunction "1_1") (pintype "passive"))
      (node (ref "C50") (pin "1") (pinfunction "1_1") (pintype "passive"))
      (node (ref "C51") (pin "1") (pinfunction "1_1") (pintype "passive"))
      (node (ref "C52") (pin "1") (pinfunction "1_1") (pintype "passive"))
      (node (ref "C53") (pin "1") (pinfunction "1_1") (pintype "passive"))
      (node (ref "C54") (pin "1") (pinfunction "1_1") (pintype "passive"))
      (node (ref "C55") (pin "1") (pinfunction "1_1") (pintype "passive"))
      (node (ref "C56") (pin "1") (pinfunction "1_1") (pintype "passive"))
      (node (ref "C57") (pin "1") (pinfunction "1_1") (pintype "passive"))
      (node (ref "C58") (pin "1") (pinfunction "1_1") (pintype "passive"))
      (node (ref "C59") (pin "1") (pinfunction "1_1") (pintype "passive"))
      (node (ref "C60") (pin "1") (pinfunction "1_1") (pintype "passive"))
      (node (ref "C61") (pin "1") (pinfunction "1_1") (pintype "passive"))
      (node (ref "C62") (pin "1") (pinfunction "1_1") (pintype "passive"))
      (node (ref "C63") (pin "1") (pinfunction "1_1") (pintype "passive"))
      (node (ref "C64") (pin "1") (pinfunction "1_1") (pintype "passive"))
      (node (ref "C65") (pin "1") (pinfunction "1_1") (pintype "passive"))
      (node (ref "C66") (pin "1") (pinfunction "1_1") (pintype "passive"))
      (node (ref "C67") (pin "1") (pinfunction "1_1") (pintype "passive"))
      (node (ref "C68") (pin "1") (pinfunction "1_1") (pintype "passive"))
      (node (ref "C69") (pin "1") (pinfunction "1_1") (pintype "passive"))
      (node (ref "C70") (pin "1") (pinfunction "1_1") (pintype "passive"))
      (node (ref "C71") (pin "1") (pinfunction "1_1") (pintype "passive"))
      (node (ref "C72") (pin "1") (pinfunction "1_1") (pintype "passive"))
      (node (ref "C73") (pin "1") (pinfunction "1_1") (pintype "passive"))
      (node (ref "C74") (pin "1") (pinfunction "1_1") (pintype "passive"))
      (node (ref "C75") (pin "1") (pinfunction "1_1") (pintype "passive"))
      (node (ref "C76") (pin "1") (pinfunction "1_1") (pintype "passive"))
      (node (ref "C77") (pin "1") (pinfunction "1_1") (pintype "passive"))
      (node (ref "C78") (pin "1") (pinfunction "1_1") (pintype "passive"))
      (node (ref "C79") (pin "1") (pinfunction "1_1") (pintype "passive"))
      (node (ref "C80") (pin "1") (pinfunction "1_1") (pintype "passive"))
      (node (ref "C81") (pin "1") (pinfunction "1_1") (pintype "passive"))
      (node (ref "C82") (pin "1") (pinfunction "1_1") (pintype "passive"))
      (node (ref "C83") (pin "1") (pinfunction "1_1") (pintype "passive"))
      (node (ref "C84") (pin "1") (pinfunction "1_1") (pintype "passive"))
      (node (ref "C85") (pin "1") (pinfunction "1_1") (pintype "passive"))
      (node (ref "C86") (pin "1") (pinfunction "1_1") (pintype "passive"))
      (node (ref "C87") (pin "1") (pinfunction "1_1") (pintype "passive"))
      (node (ref "C88") (pin "1") (pinfunction "1_1") (pintype "passive"))
      (node (ref "C89") (pin "1") (pinfunction "1_1") (pintype "passive"))
      (node (ref "C9") (pin "1") (pinfunction "1_1") (pintype "passive"))
      (node (ref "C90") (pin "1") (pinfunction "1_1") (pintype "passive"))
      (node (ref "C91") (pin "1") (pinfunction "1_1") (pintype "passive"))
      (node (ref "C92") (pin "1") (pinfunction "1_1") (pintype "passive"))
      (node (ref "C93") (pin "1") (pinfunction "1_1") (pintype "passive"))
      (node (ref "C94") (pin "1") (pinfunction "1_1") (pintype "passive"))
      (node (ref "C95") (pin "1") (pinfunction "1_1") (pintype "passive"))
      (node (ref "C96") (pin "1") (pinfunction "1_1") (pintype "passive"))
      (node (ref "C97") (pin "1") (pinfunction "1_1") (pintype "passive"))
      (node (ref "C98") (pin "1") (pinfunction "1_1") (pintype "passive"))
      (node (ref "C99") (pin "1") (pinfunction "1_1") (pintype "passive"))
      (node (ref "U2") (pin "A15") (pinfunction "GND_A15") (pintype "power_in"))
      (node (ref "U2") (pin "A5") (pinfunction "GND_A5") (pintype "power_in"))
      (node (ref "U2") (pin "AA15") (pinfunction "GND_AA15") (pintype "power_in"))
      (node (ref "U2") (pin "AA5") (pinfunction "GND_AA5") (pintype "power_in"))
      (node (ref "U2") (pin "AB18") (pinfunction "GND_AB18") (pintype "power_in"))
      (node (ref "U2") (pin "AB8") (pinfunction "GND_AB8") (pintype "power_in"))
      (node (ref "U2") (pin "B18") (pinfunction "GND_B18") (pintype "power_in"))
      (node (ref "U2") (pin "B8") (pinfunction "GND_B8") (pintype "power_in"))
      (node (ref "U2") (pin "C1") (pinfunction "GND_C1") (pintype "power_in"))
      (node (ref "U2") (pin "C11") (pinfunction "GND_C11") (pintype "power_in"))
      (node (ref "U2") (pin "C21") (pinfunction "GND_C21") (pintype "power_in"))
      (node (ref "U2") (pin "D14") (pinfunction "GND_D14") (pintype "power_in"))
      (node (ref "U2") (pin "D4") (pinfunction "GND_D4") (pintype "power_in"))
      (node (ref "U2") (pin "E17") (pinfunction "GND_E17") (pintype "power_in"))
      (node (ref "U2") (pin "E7") (pinfunction "GND_E7") (pintype "power_in"))
      (node (ref "U2") (pin "F10") (pinfunction "GND_F10") (pintype "power_in"))
      (node (ref "U2") (pin "F20") (pinfunction "GND_F20") (pintype "power_in"))
      (node (ref "U2") (pin "G3") (pinfunction "GND_G3") (pintype "power_in"))
      (node (ref "U2") (pin "H12") (pinfunction "GND_H12") (pintype "power_in"))
      (node (ref "U2") (pin "H14") (pinfunction "GND_H14") (pintype "power_in"))
      (node (ref "U2") (pin "H16") (pinfunction "GND_H16") (pintype "power_in"))
      (node (ref "U2") (pin "H6") (pinfunction "GND_H6") (pintype "power_in"))
      (node (ref "U2") (pin "H8") (pinfunction "GND_H8") (pintype "power_in"))
      (node (ref "U2") (pin "J11") (pinfunction "GND_J11") (pintype "power_in"))
      (node (ref "U2") (pin "J13") (pinfunction "GND_J13") (pintype "power_in"))
      (node (ref "U2") (pin "J19") (pinfunction "GND_J19") (pintype "power_in"))
      (node (ref "U2") (pin "J9") (pinfunction "GND_J9") (pintype "power_in"))
      (node (ref "U2") (pin "K10") (pinfunction "GND_K10") (pintype "power_in"))
      (node (ref "U2") (pin "K14") (pinfunction "GND_K14") (pintype "power_in"))
      (node (ref "U2") (pin "K2") (pinfunction "GND_K2") (pintype "power_in"))
      (node (ref "U2") (pin "K22") (pinfunction "GND_K22") (pintype "power_in"))
      (node (ref "U2") (pin "K8") (pinfunction "GND_K8") (pintype "power_in"))
      (node (ref "U2") (pin "L13") (pinfunction "GND_L13") (pintype "power_in"))
      (node (ref "U2") (pin "L15") (pinfunction "GND_L15") (pintype "power_in"))
      (node (ref "U2") (pin "L5") (pinfunction "GND_L5") (pintype "power_in"))
      (node (ref "U2") (pin "L9") (pinfunction "GND_L9") (pintype "power_in"))
      (node (ref "U2") (pin "M10") (pinfunction "GND_M10") (pintype "power_in"))
      (node (ref "U2") (pin "M14") (pinfunction "GND_M14") (pintype "power_in"))
      (node (ref "U2") (pin "M18") (pinfunction "GND_M18") (pintype "power_in"))
      (node (ref "U2") (pin "M8") (pinfunction "GND_M8") (pintype "power_in"))
      (node (ref "U2") (pin "N1") (pinfunction "GND_N1") (pintype "power_in"))
      (node (ref "U2") (pin "N13") (pinfunction "GND_N13") (pintype "power_in"))
      (node (ref "U2") (pin "N21") (pinfunction "GND_N21") (pintype "power_in"))
      (node (ref "U2") (pin "N9") (pinfunction "GND_N9") (pintype "power_in"))
      (node (ref "U2") (pin "P10") (pinfunction "GND_P10") (pintype "power_in"))
      (node (ref "U2") (pin "P12") (pinfunction "GND_P12") (pintype "power_in"))
      (node (ref "U2") (pin "P14") (pinfunction "GND_P14") (pintype "power_in"))
      (node (ref "U2") (pin "P4") (pinfunction "GND_P4") (pintype "power_in"))
      (node (ref "U2") (pin "P8") (pinfunction "GND_P8") (pintype "power_in"))
      (node (ref "U2") (pin "R11") (pinfunction "GND_R11") (pintype "power_in"))
      (node (ref "U2") (pin "R13") (pinfunction "GND_R13") (pintype "power_in"))
      (node (ref "U2") (pin "R17") (pinfunction "GND_R17") (pintype "power_in"))
      (node (ref "U2") (pin "R9") (pinfunction "GND_R9") (pintype "power_in"))
      (node (ref "U2") (pin "T20") (pinfunction "GND_T20") (pintype "power_in"))
      (node (ref "U2") (pin "U13") (pinfunction "GND_U13") (pintype "power_in"))
      (node (ref "U2") (pin "U3") (pinfunction "GND_U3") (pintype "power_in"))
      (node (ref "U2") (pin "V16") (pinfunction "GND_V16") (pintype "power_in"))
      (node (ref "U2") (pin "V6") (pinfunction "GND_V6") (pintype "power_in"))
      (node (ref "U2") (pin "W19") (pinfunction "GND_W19") (pintype "power_in"))
      (node (ref "U2") (pin "W9") (pinfunction "GND_W9") (pintype "power_in"))
      (node (ref "U2") (pin "Y12") (pinfunction "GND_Y12") (pintype "power_in"))
      (node (ref "U2") (pin "Y2") (pinfunction "GND_Y2") (pintype "power_in"))
      (node (ref "U2") (pin "Y22") (pinfunction "GND_Y22") (pintype "power_in"))
    )
    (net (code "5") (name "VADJ") (class "Default")
      (node (ref "C15") (pin "2") (pinfunction "2_2") (pintype "passive"))
      (node (ref "C16") (pin "2") (pinfunction "2_2") (pintype "passive"))
      (node (ref "C17") (pin "2") (pinfunction "2_2") (pintype "passive"))
      (node (ref "C18") (pin "2") (pinfunction "2_2") (pintype "passive"))
      (node (ref "C19") (pin "2") (pinfunction "2_2") (pintype "passive"))
      (node (ref "C20") (pin "2") (pinfunction "2_2") (pintype "passive"))
      (node (ref "C21") (pin "2") (pinfunction "2_2") (pintype "passive"))
      (node (ref "C22") (pin "2") (pinfunction "2_2") (pintype "passive"))
      (node (ref "C23") (pin "2") (pinfunction "2_2") (pintype "passive"))
      (node (ref "C24") (pin "2") (pinfunction "2_2") (pintype "passive"))
      (node (ref "C25") (pin "2") (pinfunction "2_2") (pintype "passive"))
      (node (ref "C26") (pin "2") (pinfunction "2_2") (pintype "passive"))
      (node (ref "C27") (pin "2") (pinfunction "2_2") (pintype "passive"))
      (node (ref "C39") (pin "2") (pinfunction "2_2") (pintype "passive"))
      (node (ref "C40") (pin "2") (pinfunction "2_2") (pintype "passive"))
      (node (ref "C41") (pin "2") (pinfunction "2_2") (pintype "passive"))
      (node (ref "C42") (pin "2") (pinfunction "2_2") (pintype "passive"))
      (node (ref "C43") (pin "2") (pinfunction "2_2") (pintype "passive"))
      (node (ref "C44") (pin "2") (pinfunction "2_2") (pintype "passive"))
      (node (ref "C45") (pin "2") (pinfunction "2_2") (pintype "passive"))
      (node (ref "C46") (pin "2") (pinfunction "2_2") (pintype "passive"))
      (node (ref "C47") (pin "2") (pinfunction "2_2") (pintype "passive"))
      (node (ref "C48") (pin "2") (pinfunction "2_2") (pintype "passive"))
      (node (ref "C49") (pin "2") (pinfunction "2_2") (pintype "passive"))
      (node (ref "C50") (pin "2") (pinfunction "2_2") (pintype "passive"))
      (node (ref "C51") (pin "2") (pinfunction "2_2") (pintype "passive"))
      (node (ref "U2") (pin "A20") (pinfunction "VCCO_35_A20") (pintype "power_in"))
      (node (ref "U2") (pin "C16") (pinfunction "VCCO_35_C16") (pintype "power_in"))
      (node (ref "U2") (pin "D19") (pinfunction "VCCO_35_D19") (pintype "power_in"))
      (node (ref "U2") (pin "E22") (pinfunction "VCCO_35_E22") (pintype "power_in"))
      (node (ref "U2") (pin "F15") (pinfunction "VCCO_35_F15") (pintype "power_in"))
      (node (ref "U2") (pin "G18") (pinfunction "VCCO_35_G18") (pintype "power_in"))
      (node (ref "U2") (pin "H21") (pinfunction "VCCO_35_H21") (pintype "power_in"))
      (node (ref "U2") (pin "K17") (pinfunction "VCCO_34_K17") (pintype "power_in"))
      (node (ref "U2") (pin "L20") (pinfunction "VCCO_34_L20") (pintype "power_in"))
      (node (ref "U2") (pin "N16") (pinfunction "VCCO_34_N16") (pintype "power_in"))
      (node (ref "U2") (pin "P19") (pinfunction "VCCO_34_P19") (pintype "power_in"))
      (node (ref "U2") (pin "R22") (pinfunction "VCCO_34_R22") (pintype "power_in"))
      (node (ref "U2") (pin "T15") (pinfunction "VCCO_34_T15") (pintype "power_in"))
    )
    (net (code "6") (name "VCC1V0") (class "Default")
      (node (ref "C10") (pin "2") (pinfunction "2_2") (pintype "passive"))
      (node (ref "C11") (pin "2") (pinfunction "2_2") (pintype "passive"))
      (node (ref "C12") (pin "2") (pinfunction "2_2") (pintype "passive"))
      (node (ref "C120") (pin "2") (pinfunction "2_2") (pintype "passive"))
      (node (ref "C121") (pin "2") (pinfunction "2_2") (pintype "passive"))
      (node (ref "C122") (pin "2") (pinfunction "2_2") (pintype "passive"))
      (node (ref "C123") (pin "2") (pinfunction "2_2") (pintype "passive"))
      (node (ref "C124") (pin "2") (pinfunction "2_2") (pintype "passive"))
      (node (ref "C125") (pin "2") (pinfunction "2_2") (pintype "passive"))
      (node (ref "C126") (pin "2") (pinfunction "2_2") (pintype "passive"))
      (node (ref "C127") (pin "2") (pinfunction "2_2") (pintype "passive"))
      (node (ref "C128") (pin "2") (pinfunction "2_2") (pintype "passive"))
      (node (ref "C129") (pin "2") (pinfunction "2_2") (pintype "passive"))
      (node (ref "C13") (pin "2") (pinfunction "2_2") (pintype "passive"))
      (node (ref "C130") (pin "2") (pinfunction "2_2") (pintype "passive"))
      (node (ref "C131") (pin "2") (pinfunction "2_2") (pintype "passive"))
      (node (ref "C132") (pin "2") (pinfunction "2_2") (pintype "passive"))
      (node (ref "C133") (pin "2") (pinfunction "2_2") (pintype "passive"))
      (node (ref "C134") (pin "2") (pinfunction "2_2") (pintype "passive"))
      (node (ref "C135") (pin "2") (pinfunction "2_2") (pintype "passive"))
      (node (ref "C136") (pin "2") (pinfunction "2_2") (pintype "passive"))
      (node (ref "C137") (pin "2") (pinfunction "2_2") (pintype "passive"))
      (node (ref "C138") (pin "2") (pinfunction "2_2") (pintype "passive"))
      (node (ref "C139") (pin "2") (pinfunction "2_2") (pintype "passive"))
      (node (ref "C14") (pin "2") (pinfunction "2_2") (pintype "passive"))
      (node (ref "C140") (pin "2") (pinfunction "2_2") (pintype "passive"))
      (node (ref "C141") (pin "2") (pinfunction "2_2") (pintype "passive"))
      (node (ref "C142") (pin "2") (pinfunction "2_2") (pintype "passive"))
      (node (ref "C143") (pin "2") (pinfunction "2_2") (pintype "passive"))
      (node (ref "C144") (pin "2") (pinfunction "2_2") (pintype "passive"))
      (node (ref "C145") (pin "2") (pinfunction "2_2") (pintype "passive"))
      (node (ref "C146") (pin "2") (pinfunction "2_2") (pintype "passive"))
      (node (ref "C147") (pin "2") (pinfunction "2_2") (pintype "passive"))
      (node (ref "C148") (pin "2") (pinfunction "2_2") (pintype "passive"))
      (node (ref "C149") (pin "2") (pinfunction "2_2") (pintype "passive"))
      (node (ref "C150") (pin "2") (pinfunction "2_2") (pintype "passive"))
      (node (ref "C151") (pin "2") (pinfunction "2_2") (pintype "passive"))
      (node (ref "C152") (pin "2") (pinfunction "2_2") (pintype "passive"))
      (node (ref "C153") (pin "2") (pinfunction "2_2") (pintype "passive"))
      (node (ref "C154") (pin "2") (pinfunction "2_2") (pintype "passive"))
      (node (ref "C155") (pin "2") (pinfunction "2_2") (pintype "passive"))
      (node (ref "C9") (pin "2") (pinfunction "2_2") (pintype "passive"))
      (node (ref "U2") (pin "G8") (pinfunction "VCCPINT_G8") (pintype "power_in"))
      (node (ref "U2") (pin "H11") (pinfunction "VCCBRAM_H11") (pintype "power_in"))
      (node (ref "U2") (pin "H9") (pinfunction "VCCPINT_H9") (pintype "power_in"))
      (node (ref "U2") (pin "J10") (pinfunction "VCCBRAM_J10") (pintype "power_in"))
      (node (ref "U2") (pin "J12") (pinfunction "VCCINT_J12") (pintype "power_in"))
      (node (ref "U2") (pin "J14") (pinfunction "VCCINT_J14") (pintype "power_in"))
      (node (ref "U2") (pin "J8") (pinfunction "VCCPINT_J8") (pintype "power_in"))
      (node (ref "U2") (pin "K13") (pinfunction "VCCINT_K13") (pintype "power_in"))
      (node (ref "U2") (pin "L14") (pinfunction "VCCINT_L14") (pintype "power_in"))
      (node (ref "U2") (pin "L8") (pinfunction "VCCPINT_L8") (pintype "power_in"))
      (node (ref "U2") (pin "M13") (pinfunction "VCCINT_M13") (pintype "power_in"))
      (node (ref "U2") (pin "N14") (pinfunction "VCCINT_N14") (pintype "power_in"))
      (node (ref "U2") (pin "N8") (pinfunction "VCCPINT_N8") (pintype "power_in"))
      (node (ref "U2") (pin "P13") (pinfunction "VCCINT_P13") (pintype "power_in"))
      (node (ref "U2") (pin "R14") (pinfunction "VCCINT_R14") (pintype "power_in"))
      (node (ref "U2") (pin "R8") (pinfunction "VCCPINT_R8") (pintype "power_in"))
    )
    (net (code "7") (name "VCC1V8") (class "Default")
      (node (ref "C100") (pin "2") (pinfunction "2_2") (pintype "passive"))
      (node (ref "C101") (pin "2") (pinfunction "2_2") (pintype "passive"))
      (node (ref "C102") (pin "2") (pinfunction "2_2") (pintype "passive"))
      (node (ref "C103") (pin "2") (pinfunction "2_2") (pintype "passive"))
      (node (ref "C104") (pin "2") (pinfunction "2_2") (pintype "passive"))
      (node (ref "C105") (pin "2") (pinfunction "2_2") (pintype "passive"))
      (node (ref "C106") (pin "2") (pinfunction "2_2") (pintype "passive"))
      (node (ref "C107") (pin "2") (pinfunction "2_2") (pintype "passive"))
      (node (ref "C108") (pin "2") (pinfunction "2_2") (pintype "passive"))
      (node (ref "C111") (pin "2") (pinfunction "2_2") (pintype "passive"))
      (node (ref "C112") (pin "2") (pinfunction "2_2") (pintype "passive"))
      (node (ref "C113") (pin "2") (pinfunction "2_2") (pintype "passive"))
      (node (ref "C114") (pin "2") (pinfunction "2_2") (pintype "passive"))
      (node (ref "C115") (pin "2") (pinfunction "2_2") (pintype "passive"))
      (node (ref "C116") (pin "2") (pinfunction "2_2") (pintype "passive"))
      (node (ref "C117") (pin "2") (pinfunction "2_2") (pintype "passive"))
      (node (ref "C118") (pin "2") (pinfunction "2_2") (pintype "passive"))
      (node (ref "C119") (pin "2") (pinfunction "2_2") (pintype "passive"))
      (node (ref "FB1") (pin "2") (pinfunction "2_2") (pintype "passive"))
      (node (ref "U2") (pin "K9") (pinfunction "VCCPAUX_K9") (pintype "power_in"))
      (node (ref "U2") (pin "L10") (pinfunction "VCCAUX_L10") (pintype "power_in"))
      (node (ref "U2") (pin "M9") (pinfunction "VCCPAUX_M9") (pintype "power_in"))
      (node (ref "U2") (pin "N10") (pinfunction "VCCAUX_N10") (pintype "power_in"))
      (node (ref "U2") (pin "P11") (pinfunction "VCCAUX_P11") (pintype "power_in"))
      (node (ref "U2") (pin "P9") (pinfunction "VCCPAUX_P9") (pintype "power_in"))
      (node (ref "U2") (pin "R10") (pinfunction "VCCAUX_R10") (pintype "power_in"))
      (node (ref "U2") (pin "T9") (pinfunction "VCCPAUX_T9") (pintype "power_in"))
    )
    (net (code "8") (name "VCC3V3") (class "Default")
      (node (ref "C59") (pin "2") (pinfunction "2_2") (pintype "passive"))
      (node (ref "C60") (pin "2") (pinfunction "2_2") (pintype "passive"))
      (node (ref "C61") (pin "2") (pinfunction "2_2") (pintype "passive"))
      (node (ref "C62") (pin "2") (pinfunction "2_2") (pintype "passive"))
      (node (ref "C63") (pin "2") (pinfunction "2_2") (pintype "passive"))
      (node (ref "C64") (pin "2") (pinfunction "2_2") (pintype "passive"))
      (node (ref "C65") (pin "2") (pinfunction "2_2") (pintype "passive"))
      (node (ref "C66") (pin "2") (pinfunction "2_2") (pintype "passive"))
      (node (ref "C67") (pin "2") (pinfunction "2_2") (pintype "passive"))
      (node (ref "C68") (pin "2") (pinfunction "2_2") (pintype "passive"))
      (node (ref "C69") (pin "2") (pinfunction "2_2") (pintype "passive"))
      (node (ref "C70") (pin "2") (pinfunction "2_2") (pintype "passive"))
      (node (ref "C71") (pin "2") (pinfunction "2_2") (pintype "passive"))
      (node (ref "C72") (pin "2") (pinfunction "2_2") (pintype "passive"))
      (node (ref "C73") (pin "2") (pinfunction "2_2") (pintype "passive"))
      (node (ref "C74") (pin "2") (pinfunction "2_2") (pintype "passive"))
      (node (ref "C75") (pin "2") (pinfunction "2_2") (pintype "passive"))
      (node (ref "C76") (pin "2") (pinfunction "2_2") (pintype "passive"))
      (node (ref "C77") (pin "2") (pinfunction "2_2") (pintype "passive"))
      (node (ref "C78") (pin "2") (pinfunction "2_2") (pintype "passive"))
      (node (ref "C79") (pin "2") (pinfunction "2_2") (pintype "passive"))
      (node (ref "C80") (pin "2") (pinfunction "2_2") (pintype "passive"))
      (node (ref "C81") (pin "2") (pinfunction "2_2") (pintype "passive"))
      (node (ref "C82") (pin "2") (pinfunction "2_2") (pintype "passive"))
      (node (ref "C83") (pin "2") (pinfunction "2_2") (pintype "passive"))
      (node (ref "C84") (pin "2") (pinfunction "2_2") (pintype "passive"))
      (node (ref "C85") (pin "2") (pinfunction "2_2") (pintype "passive"))
      (node (ref "C86") (pin "2") (pinfunction "2_2") (pintype "passive"))
      (node (ref "C87") (pin "2") (pinfunction "2_2") (pintype "passive"))
      (node (ref "C88") (pin "2") (pinfunction "2_2") (pintype "passive"))
      (node (ref "C89") (pin "2") (pinfunction "2_2") (pintype "passive"))
      (node (ref "C90") (pin "2") (pinfunction "2_2") (pintype "passive"))
      (node (ref "C91") (pin "2") (pinfunction "2_2") (pintype "passive"))
      (node (ref "C92") (pin "2") (pinfunction "2_2") (pintype "passive"))
      (node (ref "C93") (pin "2") (pinfunction "2_2") (pintype "passive"))
      (node (ref "C94") (pin "2") (pinfunction "2_2") (pintype "passive"))
      (node (ref "C95") (pin "2") (pinfunction "2_2") (pintype "passive"))
      (node (ref "C96") (pin "2") (pinfunction "2_2") (pintype "passive"))
      (node (ref "C97") (pin "2") (pinfunction "2_2") (pintype "passive"))
      (node (ref "C98") (pin "2") (pinfunction "2_2") (pintype "passive"))
      (node (ref "C99") (pin "2") (pinfunction "2_2") (pintype "passive"))
      (node (ref "U2") (pin "A10") (pinfunction "VCCO_MIO1_501_A10") (pintype "power_in"))
      (node (ref "U2") (pin "AA10") (pinfunction "VCCO_13_AA10") (pintype "power_in"))
      (node (ref "U2") (pin "AA20") (pinfunction "VCCO_33_AA20") (pintype "power_in"))
      (node (ref "U2") (pin "AB13") (pinfunction "VCCO_33_AB13") (pintype "power_in"))
      (node (ref "U2") (pin "AB3") (pinfunction "VCCO_13_AB3") (pintype "power_in"))
      (node (ref "U2") (pin "B13") (pinfunction "VCCO_MIO1_501_B13") (pintype "power_in"))
      (node (ref "U2") (pin "B3") (pinfunction "VCCO_MIO0_500_B3") (pintype "power_in"))
      (node (ref "U2") (pin "C6") (pinfunction "VCCO_MIO0_500_C6") (pintype "power_in"))
      (node (ref "U2") (pin "D9") (pinfunction "VCCO_MIO1_501_D9") (pintype "power_in"))
      (node (ref "U2") (pin "E12") (pinfunction "VCCO_MIO1_501_E12") (pintype "power_in"))
      (node (ref "U2") (pin "T5") (pinfunction "VCCO_13_T5") (pintype "power_in"))
      (node (ref "U2") (pin "U18") (pinfunction "VCCO_33_U18") (pintype "power_in"))
      (node (ref "U2") (pin "U8") (pinfunction "VCCO_13_U8") (pintype "power_in"))
      (node (ref "U2") (pin "V11") (pinfunction "VCCO_13_V11") (pintype "power_in"))
      (node (ref "U2") (pin "V21") (pinfunction "VCCO_33_V21") (pintype "power_in"))
      (node (ref "U2") (pin "W14") (pinfunction "VCCO_33_W14") (pintype "power_in"))
      (node (ref "U2") (pin "W4") (pinfunction "VCCO_13_W4") (pintype "power_in"))
      (node (ref "U2") (pin "Y17") (pinfunction "VCCO_33_Y17") (pintype "power_in"))
      (node (ref "U2") (pin "Y7") (pinfunction "VCCO_13_Y7") (pintype "power_in"))
    )
    (net (code "9") (name "unconnected-(U2I-VCCO_0-PadR12)") (class "Default")
      (node (ref "U2") (pin "R12") (pinfunction "VCCO_0_R12") (pintype "power_in"))
    )
  )
)
